# SparkFun_Stepoko.net
KiCad netlist of a schematic drawn in EAGLE
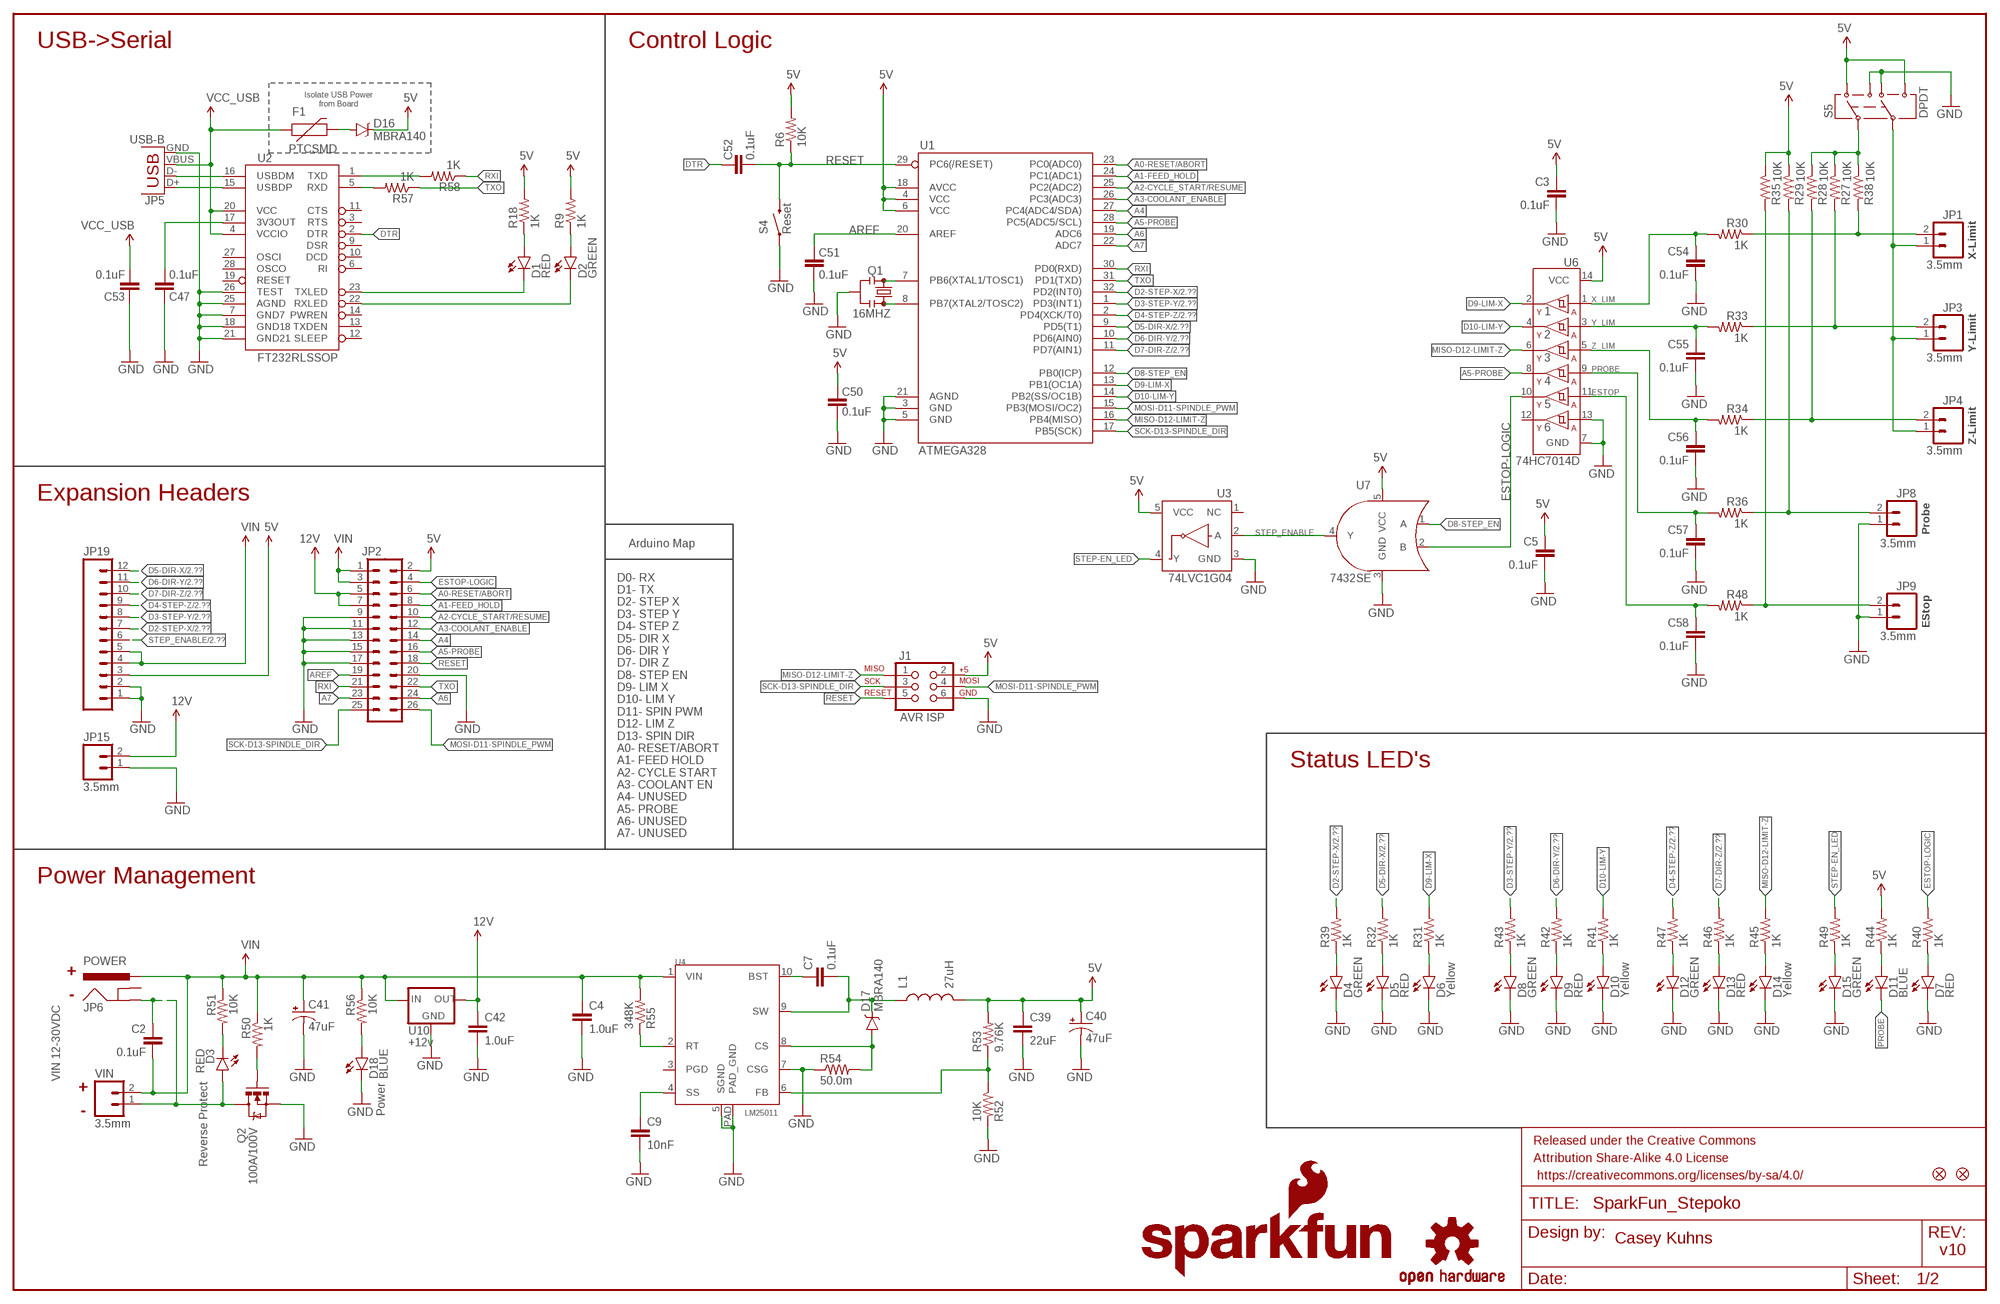
[diagram p0: schematic, sheet 1]
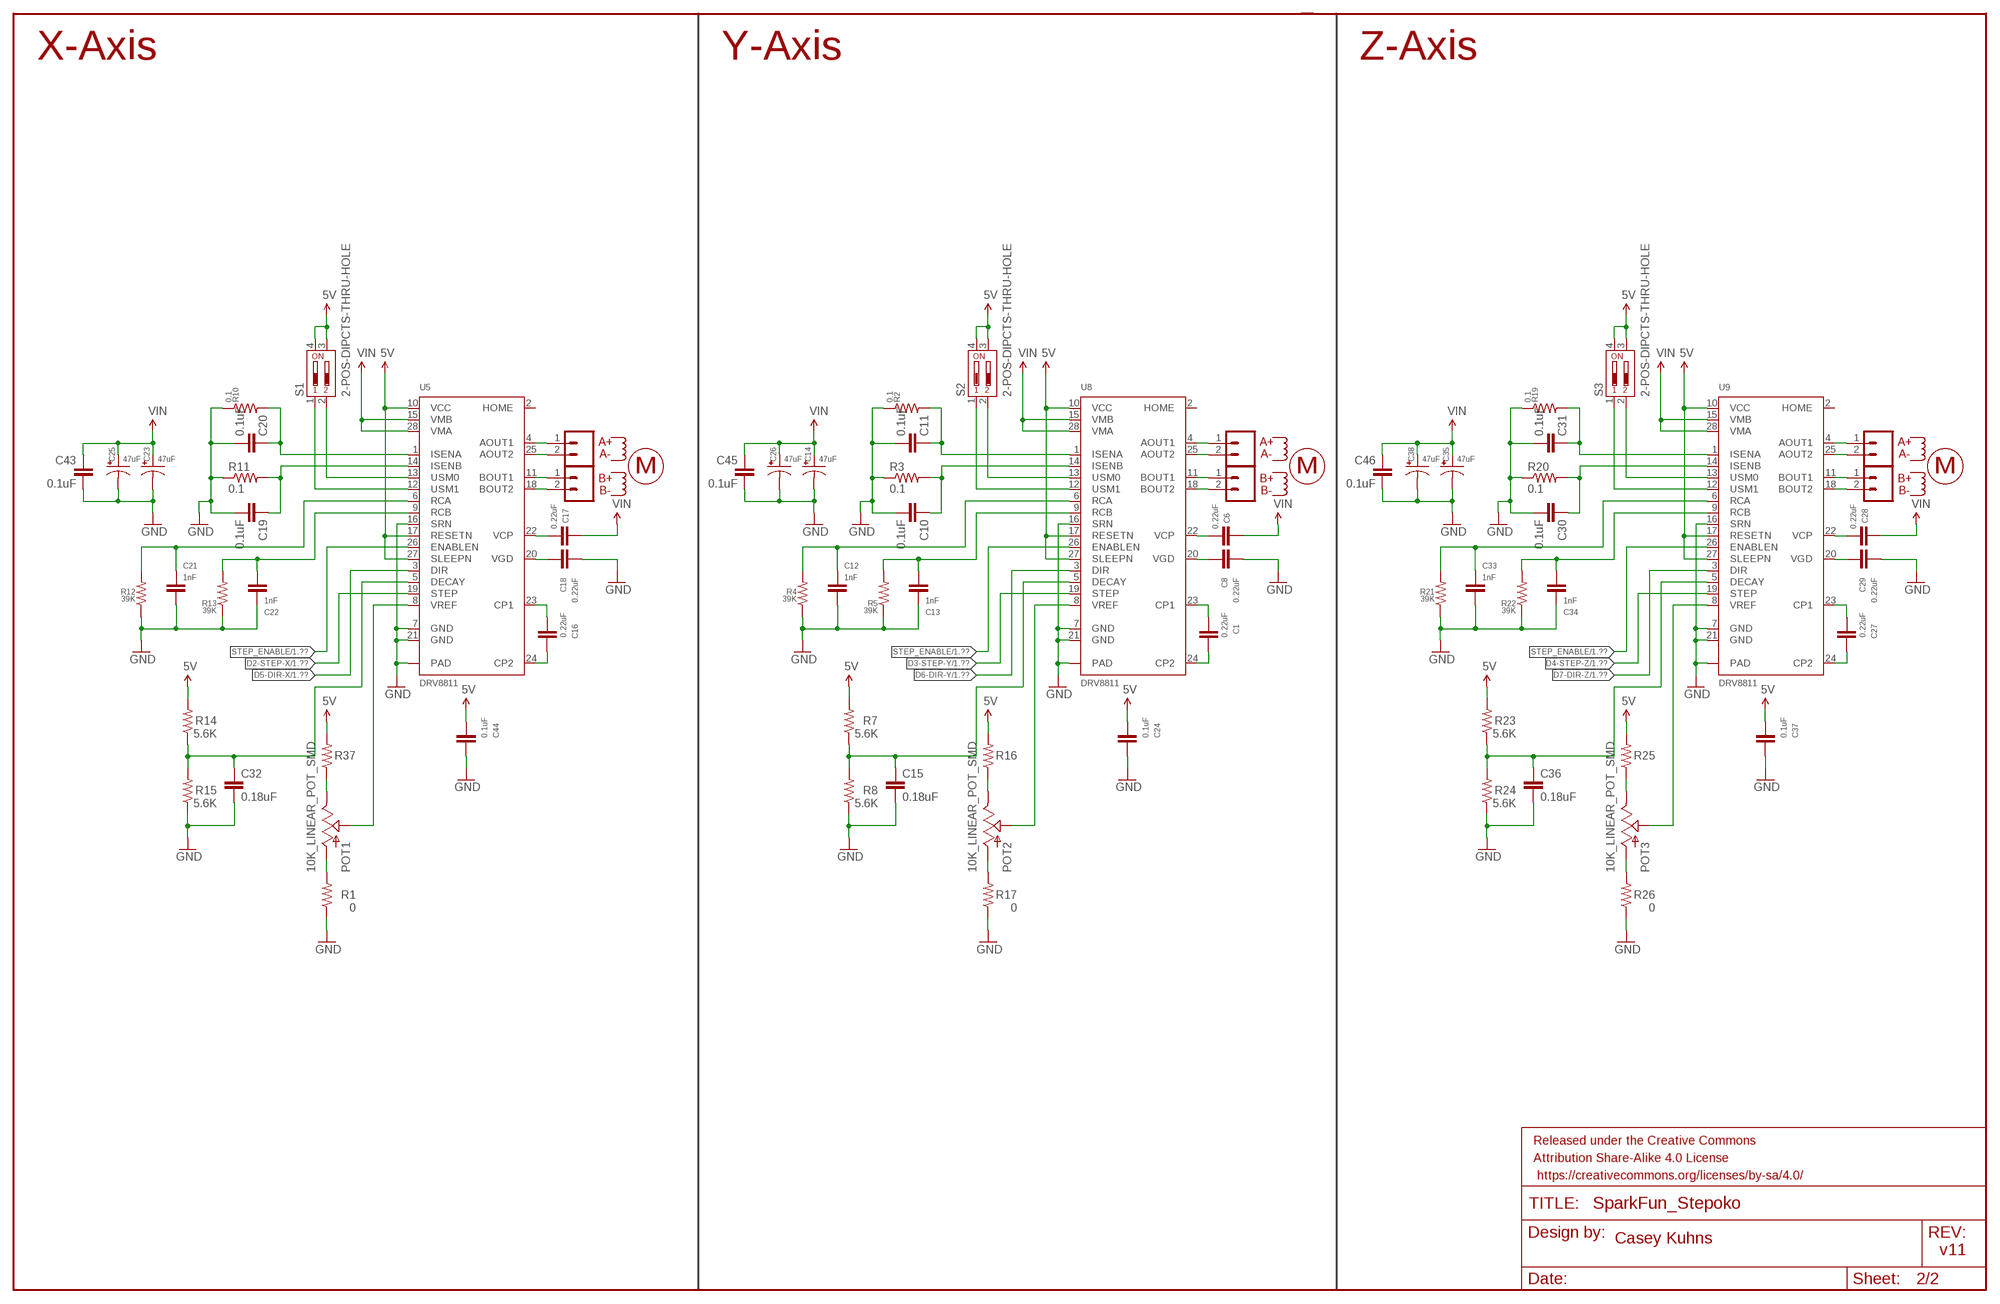
[diagram p1: schematic, sheet 2]

(export (version "E")
  (design (tool "Eeschema 10.0.6"))
  (components
    (comp (ref "C1")
      (value "0.22uF")
      (footprint "eagle-import:0603-CAP")
      (libsource (lib "eagle-import") (part "0.22UF50V-20%,+80%(0603)"))
    )
    (comp (ref "C6")
      (value "0.22uF")
      (footprint "eagle-import:0603-CAP")
      (libsource (lib "eagle-import") (part "0.22UF50V-20%,+80%(0603)"))
    )
    (comp (ref "C8")
      (value "0.22uF")
      (footprint "eagle-import:0603-CAP")
      (libsource (lib "eagle-import") (part "0.22UF50V-20%,+80%(0603)"))
    )
    (comp (ref "C10")
      (value "0.1uF")
      (footprint "eagle-import:0603-CAP")
      (libsource (lib "eagle-import") (part "0.1UF-25V(+80/-20%)(0603)"))
    )
    (comp (ref "C11")
      (value "0.1uF")
      (footprint "eagle-import:0603-CAP")
      (libsource (lib "eagle-import") (part "0.1UF-25V(+80/-20%)(0603)"))
    )
    (comp (ref "C12")
      (value "1nF")
      (footprint "eagle-import:0603-CAP")
      (libsource (lib "eagle-import") (part "1NF/1000PF-50V-10%(0603)"))
    )
    (comp (ref "C13")
      (value "1nF")
      (footprint "eagle-import:0603-CAP")
      (libsource (lib "eagle-import") (part "1NF/1000PF-50V-10%(0603)"))
    )
    (comp (ref "C14")
      (value "47uF")
      (footprint "eagle-import:PANASONIC_D")
      (libsource (lib "eagle-import") (part "47UF-50V-20%(ELECT)"))
    )
    (comp (ref "C15")
      (value "0.18uF")
      (footprint "eagle-import:0603")
      (libsource (lib "eagle-import") (part "0.18UF-10V(+-10%)(0603)"))
    )
    (comp (ref "C16")
      (value "0.22uF")
      (footprint "eagle-import:0603-CAP")
      (libsource (lib "eagle-import") (part "0.22UF50V-20%,+80%(0603)"))
    )
    (comp (ref "C17")
      (value "0.22uF")
      (footprint "eagle-import:0603-CAP")
      (libsource (lib "eagle-import") (part "0.22UF50V-20%,+80%(0603)"))
    )
    (comp (ref "C18")
      (value "0.22uF")
      (footprint "eagle-import:0603-CAP")
      (libsource (lib "eagle-import") (part "0.22UF50V-20%,+80%(0603)"))
    )
    (comp (ref "C19")
      (value "0.1uF")
      (footprint "eagle-import:0603-CAP")
      (libsource (lib "eagle-import") (part "0.1UF-25V(+80/-20%)(0603)"))
    )
    (comp (ref "C20")
      (value "0.1uF")
      (footprint "eagle-import:0603-CAP")
      (libsource (lib "eagle-import") (part "0.1UF-25V(+80/-20%)(0603)"))
    )
    (comp (ref "C21")
      (value "1nF")
      (footprint "eagle-import:0603-CAP")
      (libsource (lib "eagle-import") (part "1NF/1000PF-50V-10%(0603)"))
    )
    (comp (ref "C22")
      (value "1nF")
      (footprint "eagle-import:0603-CAP")
      (libsource (lib "eagle-import") (part "1NF/1000PF-50V-10%(0603)"))
    )
    (comp (ref "C23")
      (value "47uF")
      (footprint "eagle-import:PANASONIC_D")
      (libsource (lib "eagle-import") (part "47UF-50V-20%(ELECT)"))
    )
    (comp (ref "C24")
      (value "0.1uF")
      (footprint "eagle-import:0603-CAP")
      (libsource (lib "eagle-import") (part "0.1UF-25V(+80/-20%)(0603)"))
    )
    (comp (ref "C25")
      (value "47uF")
      (footprint "eagle-import:PANASONIC_D")
      (libsource (lib "eagle-import") (part "47UF-50V-20%(ELECT)"))
    )
    (comp (ref "C26")
      (value "47uF")
      (footprint "eagle-import:PANASONIC_D")
      (libsource (lib "eagle-import") (part "47UF-50V-20%(ELECT)"))
    )
    (comp (ref "C27")
      (value "0.22uF")
      (footprint "eagle-import:0603-CAP")
      (libsource (lib "eagle-import") (part "0.22UF50V-20%,+80%(0603)"))
    )
    (comp (ref "C28")
      (value "0.22uF")
      (footprint "eagle-import:0603-CAP")
      (libsource (lib "eagle-import") (part "0.22UF50V-20%,+80%(0603)"))
    )
    (comp (ref "C29")
      (value "0.22uF")
      (footprint "eagle-import:0603-CAP")
      (libsource (lib "eagle-import") (part "0.22UF50V-20%,+80%(0603)"))
    )
    (comp (ref "C30")
      (value "0.1uF")
      (footprint "eagle-import:0603-CAP")
      (libsource (lib "eagle-import") (part "0.1UF-25V(+80/-20%)(0603)"))
    )
    (comp (ref "C31")
      (value "0.1uF")
      (footprint "eagle-import:0603-CAP")
      (libsource (lib "eagle-import") (part "0.1UF-25V(+80/-20%)(0603)"))
    )
    (comp (ref "C32")
      (value "0.18uF")
      (footprint "eagle-import:0603")
      (libsource (lib "eagle-import") (part "0.18UF-10V(+-10%)(0603)"))
    )
    (comp (ref "C33")
      (value "1nF")
      (footprint "eagle-import:0603-CAP")
      (libsource (lib "eagle-import") (part "1NF/1000PF-50V-10%(0603)"))
    )
    (comp (ref "C34")
      (value "1nF")
      (footprint "eagle-import:0603-CAP")
      (libsource (lib "eagle-import") (part "1NF/1000PF-50V-10%(0603)"))
    )
    (comp (ref "C35")
      (value "47uF")
      (footprint "eagle-import:PANASONIC_D")
      (libsource (lib "eagle-import") (part "47UF-50V-20%(ELECT)"))
    )
    (comp (ref "C36")
      (value "0.18uF")
      (footprint "eagle-import:0603")
      (libsource (lib "eagle-import") (part "0.18UF-10V(+-10%)(0603)"))
    )
    (comp (ref "C37")
      (value "0.1uF")
      (footprint "eagle-import:0603-CAP")
      (libsource (lib "eagle-import") (part "0.1UF-25V(+80/-20%)(0603)"))
    )
    (comp (ref "C38")
      (value "47uF")
      (footprint "eagle-import:PANASONIC_D")
      (libsource (lib "eagle-import") (part "47UF-50V-20%(ELECT)"))
    )
    (comp (ref "C43")
      (value "0.1uF")
      (footprint "eagle-import:0603-CAP")
      (libsource (lib "eagle-import") (part "0.1UF-100V-10%(0603)"))
    )
    (comp (ref "C44")
      (value "0.1uF")
      (footprint "eagle-import:0603-CAP")
      (libsource (lib "eagle-import") (part "0.1UF-25V(+80/-20%)(0603)"))
    )
    (comp (ref "C45")
      (value "0.1uF")
      (footprint "eagle-import:0603-CAP")
      (libsource (lib "eagle-import") (part "0.1UF-100V-10%(0603)"))
    )
    (comp (ref "C46")
      (value "0.1uF")
      (footprint "eagle-import:0603-CAP")
      (libsource (lib "eagle-import") (part "0.1UF-100V-10%(0603)"))
    )
    (comp (ref "FRAME2")
      (value "FRAME-LEDGER")
      (footprint "eagle-import:CREATIVE_COMMONS")
      (fields (field (name "DESIGNER") "Casey Kuhns") (field (name "VERSION") "v02"))
      (libsource (lib "eagle-import") (part "FRAME-LEDGER"))
    )
    (comp (ref "POT1")
      (value "10K_LINEAR_POT_SMD")
      (footprint "eagle-import:TC33X")
      (libsource (lib "eagle-import") (part "10K_LINEAR_POT_SMD"))
    )
    (comp (ref "POT2")
      (value "10K_LINEAR_POT_SMD")
      (footprint "eagle-import:TC33X")
      (libsource (lib "eagle-import") (part "10K_LINEAR_POT_SMD"))
    )
    (comp (ref "POT3")
      (value "10K_LINEAR_POT_SMD")
      (footprint "eagle-import:TC33X")
      (libsource (lib "eagle-import") (part "10K_LINEAR_POT_SMD"))
    )
    (comp (ref "R1")
      (value "0")
      (footprint "eagle-import:0603")
      (libsource (lib "eagle-import") (part "0OHM-1/10W-5%(0603)"))
    )
    (comp (ref "R2")
      (value "0.1")
      (footprint "eagle-import:1210")
      (libsource (lib "eagle-import") (part "0.1OHM-1/2W-1%(1210)"))
    )
    (comp (ref "R3")
      (value "0.1")
      (footprint "eagle-import:1210")
      (libsource (lib "eagle-import") (part "0.1OHM-1/2W-1%(1210)"))
    )
    (comp (ref "R4")
      (value "39K")
      (footprint "eagle-import:0603")
      (libsource (lib "eagle-import") (part "39KOHM-1/10W-1%(0603)"))
    )
    (comp (ref "R5")
      (value "39K")
      (footprint "eagle-import:0603")
      (libsource (lib "eagle-import") (part "39KOHM-1/10W-1%(0603)"))
    )
    (comp (ref "R7")
      (value "5.6K")
      (footprint "eagle-import:0603")
      (libsource (lib "eagle-import") (part "5.6KOHM-1/10W-1%(0603)"))
    )
    (comp (ref "R8")
      (value "5.6K")
      (footprint "eagle-import:0603")
      (libsource (lib "eagle-import") (part "5.6KOHM-1/10W-1%(0603)"))
    )
    (comp (ref "R10")
      (value "0.1")
      (footprint "eagle-import:1210")
      (libsource (lib "eagle-import") (part "0.1OHM-1/2W-1%(1210)"))
    )
    (comp (ref "R11")
      (value "0.1")
      (footprint "eagle-import:1210")
      (libsource (lib "eagle-import") (part "0.1OHM-1/2W-1%(1210)"))
    )
    (comp (ref "R12")
      (value "39K")
      (footprint "eagle-import:0603")
      (libsource (lib "eagle-import") (part "39KOHM-1/10W-1%(0603)"))
    )
    (comp (ref "R13")
      (value "39K")
      (footprint "eagle-import:0603")
      (libsource (lib "eagle-import") (part "39KOHM-1/10W-1%(0603)"))
    )
    (comp (ref "R14")
      (value "5.6K")
      (footprint "eagle-import:0603")
      (libsource (lib "eagle-import") (part "5.6KOHM-1/10W-1%(0603)"))
    )
    (comp (ref "R15")
      (value "5.6K")
      (footprint "eagle-import:0603")
      (libsource (lib "eagle-import") (part "5.6KOHM-1/10W-1%(0603)"))
    )
    (comp (ref "R16")
      (value "10K")
      (footprint "eagle-import:0603-RES")
      (libsource (lib "eagle-import") (part "10KOHM-1/10W-1%(0603)0603"))
    )
    (comp (ref "R17")
      (value "0")
      (footprint "eagle-import:0603")
      (libsource (lib "eagle-import") (part "0OHM-1/10W-5%(0603)"))
    )
    (comp (ref "R19")
      (value "0.1")
      (footprint "eagle-import:1210")
      (libsource (lib "eagle-import") (part "0.1OHM-1/2W-1%(1210)"))
    )
    (comp (ref "R20")
      (value "0.1")
      (footprint "eagle-import:1210")
      (libsource (lib "eagle-import") (part "0.1OHM-1/2W-1%(1210)"))
    )
    (comp (ref "R21")
      (value "39K")
      (footprint "eagle-import:0603")
      (libsource (lib "eagle-import") (part "39KOHM-1/10W-1%(0603)"))
    )
    (comp (ref "R22")
      (value "39K")
      (footprint "eagle-import:0603")
      (libsource (lib "eagle-import") (part "39KOHM-1/10W-1%(0603)"))
    )
    (comp (ref "R23")
      (value "5.6K")
      (footprint "eagle-import:0603")
      (libsource (lib "eagle-import") (part "5.6KOHM-1/10W-1%(0603)"))
    )
    (comp (ref "R24")
      (value "5.6K")
      (footprint "eagle-import:0603")
      (libsource (lib "eagle-import") (part "5.6KOHM-1/10W-1%(0603)"))
    )
    (comp (ref "R25")
      (value "10K")
      (footprint "eagle-import:0603-RES")
      (libsource (lib "eagle-import") (part "10KOHM-1/10W-1%(0603)0603"))
    )
    (comp (ref "R26")
      (value "0")
      (footprint "eagle-import:0603")
      (libsource (lib "eagle-import") (part "0OHM-1/10W-5%(0603)"))
    )
    (comp (ref "R37")
      (value "10K")
      (footprint "eagle-import:0603-RES")
      (libsource (lib "eagle-import") (part "10KOHM-1/10W-1%(0603)0603"))
    )
    (comp (ref "S1")
      (value "2-POS-DIPCTS-THRU-HOLE")
      (footprint "eagle-import:209-2LPST")
      (libsource (lib "eagle-import") (part "2-POS-DIPCTS-THRU-HOLE"))
    )
    (comp (ref "S2")
      (value "2-POS-DIPCTS-THRU-HOLE")
      (footprint "eagle-import:209-2LPST")
      (libsource (lib "eagle-import") (part "2-POS-DIPCTS-THRU-HOLE"))
    )
    (comp (ref "S3")
      (value "2-POS-DIPCTS-THRU-HOLE")
      (footprint "eagle-import:209-2LPST")
      (libsource (lib "eagle-import") (part "2-POS-DIPCTS-THRU-HOLE"))
    )
    (comp (ref "U5")
      (value "DRV8811")
      (footprint "eagle-import:HTSSOP28")
      (libsource (lib "eagle-import") (part "DRV8811"))
    )
    (comp (ref "U8")
      (value "DRV8811")
      (footprint "eagle-import:HTSSOP28")
      (libsource (lib "eagle-import") (part "DRV8811"))
    )
    (comp (ref "U9")
      (value "DRV8811")
      (footprint "eagle-import:HTSSOP28")
      (libsource (lib "eagle-import") (part "DRV8811"))
    )
    (comp (ref "X-A")
      (value "3.5mm")
      (footprint "eagle-import:SCREWTERMINAL-3.5MM-2_LOCK")
      (libsource (lib "eagle-import") (part "M023.5MM_LOCK"))
    )
    (comp (ref "X-B")
      (value "3.5mm")
      (footprint "eagle-import:SCREWTERMINAL-3.5MM-2_LOCK")
      (libsource (lib "eagle-import") (part "M023.5MM_LOCK"))
    )
    (comp (ref "Y-A")
      (value "3.5mm")
      (footprint "eagle-import:SCREWTERMINAL-3.5MM-2_LOCK")
      (libsource (lib "eagle-import") (part "M023.5MM_LOCK"))
    )
    (comp (ref "Y-B")
      (value "3.5mm")
      (footprint "eagle-import:SCREWTERMINAL-3.5MM-2_LOCK")
      (libsource (lib "eagle-import") (part "M023.5MM_LOCK"))
    )
    (comp (ref "Z-A")
      (value "3.5mm")
      (footprint "eagle-import:SCREWTERMINAL-3.5MM-2_LOCK")
      (libsource (lib "eagle-import") (part "M023.5MM_LOCK"))
    )
    (comp (ref "Z-B")
      (value "3.5mm")
      (footprint "eagle-import:SCREWTERMINAL-3.5MM-2_LOCK")
      (libsource (lib "eagle-import") (part "M023.5MM_LOCK"))
    )
    (comp (ref "C2")
      (value "0.1uF")
      (footprint "eagle-import:0603-CAP")
      (libsource (lib "eagle-import") (part "0.1UF-100V-10%(0603)"))
    )
    (comp (ref "C3")
      (value "0.1uF")
      (footprint "eagle-import:0603-CAP")
      (libsource (lib "eagle-import") (part "0.1UF-25V(+80/-20%)(0603)"))
    )
    (comp (ref "C4")
      (value "1.0uF")
      (footprint "eagle-import:1206-CAP")
      (libsource (lib "eagle-import") (part "1.0UF50V10%(1206)"))
    )
    (comp (ref "C5")
      (value "0.1uF")
      (footprint "eagle-import:0603-CAP")
      (libsource (lib "eagle-import") (part "0.1UF-25V(+80/-20%)(0603)"))
    )
    (comp (ref "C7")
      (value "0.1uF")
      (footprint "eagle-import:0603-CAP")
      (libsource (lib "eagle-import") (part "0.1UF-25V(+80/-20%)(0603)"))
    )
    (comp (ref "C9")
      (value "10nF")
      (footprint "eagle-import:0603-CAP")
      (libsource (lib "eagle-import") (part "10NF/10000PF-50V-10%(0603)"))
    )
    (comp (ref "C39")
      (value "22uF")
      (footprint "eagle-import:1210")
      (libsource (lib "eagle-import") (part "22UF-16V-20%-(1210)"))
    )
    (comp (ref "C40")
      (value "47uF")
      (footprint "eagle-import:PANASONIC_D")
      (libsource (lib "eagle-import") (part "47UF-50V-20%(ELECT)"))
    )
    (comp (ref "C41")
      (value "47uF")
      (footprint "eagle-import:PANASONIC_D")
      (libsource (lib "eagle-import") (part "47UF-50V-20%(ELECT)"))
    )
    (comp (ref "C42")
      (value "1.0uF")
      (footprint "eagle-import:1206-CAP")
      (libsource (lib "eagle-import") (part "1.0UF50V10%(1206)"))
    )
    (comp (ref "C47")
      (value "0.1uF")
      (footprint "eagle-import:0603-CAP")
      (libsource (lib "eagle-import") (part "0.1UF-25V(+80/-20%)(0603)"))
    )
    (comp (ref "C50")
      (value "0.1uF")
      (footprint "eagle-import:0603-CAP")
      (libsource (lib "eagle-import") (part "0.1UF-25V(+80/-20%)(0603)"))
    )
    (comp (ref "C51")
      (value "0.1uF")
      (footprint "eagle-import:0603-CAP")
      (libsource (lib "eagle-import") (part "0.1UF-25V(+80/-20%)(0603)"))
    )
    (comp (ref "C52")
      (value "0.1uF")
      (footprint "eagle-import:0603-CAP")
      (libsource (lib "eagle-import") (part "0.1UF-25V(+80/-20%)(0603)"))
    )
    (comp (ref "C53")
      (value "0.1uF")
      (footprint "eagle-import:0603-CAP")
      (libsource (lib "eagle-import") (part "0.1UF-25V(+80/-20%)(0603)"))
    )
    (comp (ref "C54")
      (value "0.1uF")
      (footprint "eagle-import:0603-CAP")
      (libsource (lib "eagle-import") (part "0.1UF-25V(+80/-20%)(0603)"))
    )
    (comp (ref "C55")
      (value "0.1uF")
      (footprint "eagle-import:0603-CAP")
      (libsource (lib "eagle-import") (part "0.1UF-25V(+80/-20%)(0603)"))
    )
    (comp (ref "C56")
      (value "0.1uF")
      (footprint "eagle-import:0603-CAP")
      (libsource (lib "eagle-import") (part "0.1UF-25V(+80/-20%)(0603)"))
    )
    (comp (ref "C57")
      (value "0.1uF")
      (footprint "eagle-import:0603-CAP")
      (libsource (lib "eagle-import") (part "0.1UF-25V(+80/-20%)(0603)"))
    )
    (comp (ref "C58")
      (value "0.1uF")
      (footprint "eagle-import:0603-CAP")
      (libsource (lib "eagle-import") (part "0.1UF-25V(+80/-20%)(0603)"))
    )
    (comp (ref "D1")
      (value "RED")
      (footprint "eagle-import:LED-1206")
      (libsource (lib "eagle-import") (part "LED-REDLILYPAD"))
    )
    (comp (ref "D2")
      (value "GREEN")
      (footprint "eagle-import:LED-1206")
      (libsource (lib "eagle-import") (part "LED-GREENLILYPAD"))
    )
    (comp (ref "D3")
      (value "RED")
      (footprint "eagle-import:LED-1206")
      (libsource (lib "eagle-import") (part "LED-REDLILYPAD"))
    )
    (comp (ref "D4")
      (value "GREEN")
      (footprint "eagle-import:LED-1206")
      (libsource (lib "eagle-import") (part "LED-GREENLILYPAD"))
    )
    (comp (ref "D5")
      (value "RED")
      (footprint "eagle-import:LED-1206")
      (libsource (lib "eagle-import") (part "LED-REDLILYPAD"))
    )
    (comp (ref "D6")
      (value "Yellow")
      (footprint "eagle-import:LED-1206")
      (libsource (lib "eagle-import") (part "LED-YELLOWLILYPAD"))
    )
    (comp (ref "D7")
      (value "RED")
      (footprint "eagle-import:LED-1206")
      (libsource (lib "eagle-import") (part "LED-REDLILYPAD"))
    )
    (comp (ref "D8")
      (value "GREEN")
      (footprint "eagle-import:LED-1206")
      (libsource (lib "eagle-import") (part "LED-GREENLILYPAD"))
    )
    (comp (ref "D9")
      (value "RED")
      (footprint "eagle-import:LED-1206")
      (libsource (lib "eagle-import") (part "LED-REDLILYPAD"))
    )
    (comp (ref "D10")
      (value "Yellow")
      (footprint "eagle-import:LED-1206")
      (libsource (lib "eagle-import") (part "LED-YELLOWLILYPAD"))
    )
    (comp (ref "D11")
      (value "BLUE")
      (footprint "eagle-import:LED-1206")
      (libsource (lib "eagle-import") (part "LED-BLUE1206"))
    )
    (comp (ref "D12")
      (value "GREEN")
      (footprint "eagle-import:LED-1206")
      (libsource (lib "eagle-import") (part "LED-GREENLILYPAD"))
    )
    (comp (ref "D13")
      (value "RED")
      (footprint "eagle-import:LED-1206")
      (libsource (lib "eagle-import") (part "LED-REDLILYPAD"))
    )
    (comp (ref "D14")
      (value "Yellow")
      (footprint "eagle-import:LED-1206")
      (libsource (lib "eagle-import") (part "LED-YELLOWLILYPAD"))
    )
    (comp (ref "D15")
      (value "GREEN")
      (footprint "eagle-import:LED-1206")
      (libsource (lib "eagle-import") (part "LED-GREENLILYPAD"))
    )
    (comp (ref "D16")
      (value "MBRA140")
      (footprint "eagle-import:SMA-DIODE")
      (libsource (lib "eagle-import") (part "DIODE-SCHOTTKY-MBRA140"))
    )
    (comp (ref "D17")
      (value "MBRA140")
      (footprint "eagle-import:SMA-DIODE")
      (libsource (lib "eagle-import") (part "DIODE-SCHOTTKY-MBRA140"))
    )
    (comp (ref "D18")
      (value "BLUE")
      (footprint "eagle-import:LED-1206")
      (libsource (lib "eagle-import") (part "LED-BLUE1206"))
    )
    (comp (ref "F1")
      (value "PTCSMD")
      (footprint "eagle-import:PTC-1206")
      (libsource (lib "eagle-import") (part "PTCSMD"))
    )
    (comp (ref "FID1")
      (value "FIDUCIAL1X2")
      (footprint "eagle-import:FIDUCIAL-1X2")
      (libsource (lib "eagle-import") (part "FIDUCIAL1X2"))
    )
    (comp (ref "FID2")
      (value "FIDUCIAL1X2")
      (footprint "eagle-import:FIDUCIAL-1X2")
      (libsource (lib "eagle-import") (part "FIDUCIAL1X2"))
    )
    (comp (ref "FRAME1")
      (value "FRAME-LEDGER")
      (footprint "eagle-import:CREATIVE_COMMONS")
      (fields (field (name "DESIGNER") "Casey Kuhns") (field (name "VERSION") "v02"))
      (libsource (lib "eagle-import") (part "FRAME-LEDGER"))
    )
    (comp (ref "J1")
      (value "AVR ISP")
      (footprint "eagle-import:2X3")
      (libsource (lib "eagle-import") (part "AVR_SPI_PRG_6PTH"))
    )
    (comp (ref "JP1")
      (value "3.5mm")
      (footprint "eagle-import:SCREWTERMINAL-3.5MM-2_LOCK")
      (libsource (lib "eagle-import") (part "M023.5MM_LOCK"))
    )
    (comp (ref "JP2")
      (value "M13X22X13")
      (footprint "eagle-import:2X13")
      (libsource (lib "eagle-import") (part "M13X22X13"))
    )
    (comp (ref "JP3")
      (value "3.5mm")
      (footprint "eagle-import:SCREWTERMINAL-3.5MM-2_LOCK")
      (libsource (lib "eagle-import") (part "M023.5MM_LOCK"))
    )
    (comp (ref "JP4")
      (value "3.5mm")
      (footprint "eagle-import:SCREWTERMINAL-3.5MM-2_LOCK")
      (libsource (lib "eagle-import") (part "M023.5MM_LOCK"))
    )
    (comp (ref "JP5")
      (value "USB-B")
      (footprint "eagle-import:USB-B-PTH")
      (libsource (lib "eagle-import") (part "USBPTH"))
    )
    (comp (ref "JP6")
      (value "POWER")
      (footprint "eagle-import:POWER_JACK_PTH_LOCK")
      (libsource (lib "eagle-import") (part "POWER_JACKPTH_LOCK"))
    )
    (comp (ref "JP8")
      (value "3.5mm")
      (footprint "eagle-import:SCREWTERMINAL-3.5MM-2_LOCK")
      (libsource (lib "eagle-import") (part "M023.5MM_LOCK"))
    )
    (comp (ref "JP9")
      (value "3.5mm")
      (footprint "eagle-import:SCREWTERMINAL-3.5MM-2_LOCK")
      (libsource (lib "eagle-import") (part "M023.5MM_LOCK"))
    )
    (comp (ref "JP15")
      (value "3.5mm")
      (footprint "eagle-import:SCREWTERMINAL-3.5MM-2_LOCK")
      (libsource (lib "eagle-import") (part "M023.5MM_LOCK"))
    )
    (comp (ref "JP19")
      (value "M12PTH")
      (footprint "eagle-import:1X12")
      (libsource (lib "eagle-import") (part "M12PTH"))
    )
    (comp (ref "L1")
      (value "27uH")
      (footprint "eagle-import:INDUCTOR_SDR1307")
      (libsource (lib "eagle-import") (part "INDUCTORSDR13-7-270ML"))
    )
    (comp (ref "LOGO1")
      (value "OSHW-LOGOM")
      (footprint "eagle-import:OSHW-LOGO-M")
      (libsource (lib "eagle-import") (part "OSHW-LOGOM"))
    )
    (comp (ref "LOGO3")
      (value "SFE_LOGO_NAME_FLAME.2_INCH")
      (footprint "eagle-import:SFE_LOGO_NAME_FLAME_.2")
      (libsource (lib "eagle-import") (part "SFE_LOGO_NAME_FLAME.2_INCH"))
    )
    (comp (ref "Q1")
      (value "16MHZ")
      (footprint "eagle-import:RESONATOR-SMD")
      (libsource (lib "eagle-import") (part "RESONATOR16MHZ"))
    )
    (comp (ref "Q2")
      (value "100A/100V")
      (footprint "eagle-import:TO-263_D2PAK")
      (libsource (lib "eagle-import") (part "MOSFET-NCHANNELPSMN7R0"))
    )
    (comp (ref "R6")
      (value "10K")
      (footprint "eagle-import:0603-RES")
      (libsource (lib "eagle-import") (part "10KOHM-1/10W-1%(0603)0603"))
    )
    (comp (ref "R9")
      (value "1K")
      (footprint "eagle-import:0603-RES@1")
      (libsource (lib "eagle-import") (part "1KOHM1/10W1%(0603)"))
    )
    (comp (ref "R18")
      (value "1K")
      (footprint "eagle-import:0603-RES@1")
      (libsource (lib "eagle-import") (part "1KOHM1/10W1%(0603)"))
    )
    (comp (ref "R27")
      (value "10K")
      (footprint "eagle-import:0603-RES")
      (libsource (lib "eagle-import") (part "10KOHM-1/10W-1%(0603)0603"))
    )
    (comp (ref "R28")
      (value "10K")
      (footprint "eagle-import:0603-RES")
      (libsource (lib "eagle-import") (part "10KOHM-1/10W-1%(0603)0603"))
    )
    (comp (ref "R29")
      (value "10K")
      (footprint "eagle-import:0603-RES")
      (libsource (lib "eagle-import") (part "10KOHM-1/10W-1%(0603)0603"))
    )
    (comp (ref "R30")
      (value "1K")
      (footprint "eagle-import:0603-RES@1")
      (libsource (lib "eagle-import") (part "1KOHM1/10W1%(0603)"))
    )
    (comp (ref "R31")
      (value "1K")
      (footprint "eagle-import:0603-RES")
      (libsource (lib "eagle-import") (part "1KOHM-1/10W-1%(0603)"))
    )
    (comp (ref "R32")
      (value "1K")
      (footprint "eagle-import:0603-RES")
      (libsource (lib "eagle-import") (part "1KOHM-1/10W-1%(0603)"))
    )
    (comp (ref "R33")
      (value "1K")
      (footprint "eagle-import:0603-RES@1")
      (libsource (lib "eagle-import") (part "1KOHM1/10W1%(0603)"))
    )
    (comp (ref "R34")
      (value "1K")
      (footprint "eagle-import:0603-RES@1")
      (libsource (lib "eagle-import") (part "1KOHM1/10W1%(0603)"))
    )
    (comp (ref "R35")
      (value "10K")
      (footprint "eagle-import:0603-RES")
      (libsource (lib "eagle-import") (part "10KOHM-1/10W-1%(0603)0603"))
    )
    (comp (ref "R36")
      (value "1K")
      (footprint "eagle-import:0603-RES@1")
      (libsource (lib "eagle-import") (part "1KOHM1/10W1%(0603)"))
    )
    (comp (ref "R38")
      (value "10K")
      (footprint "eagle-import:0603-RES")
      (libsource (lib "eagle-import") (part "10KOHM-1/10W-1%(0603)0603"))
    )
    (comp (ref "R39")
      (value "1K")
      (footprint "eagle-import:0603-RES")
      (libsource (lib "eagle-import") (part "1KOHM-1/10W-1%(0603)"))
    )
    (comp (ref "R40")
      (value "1K")
      (footprint "eagle-import:0603-RES")
      (libsource (lib "eagle-import") (part "1KOHM-1/10W-1%(0603)"))
    )
    (comp (ref "R41")
      (value "1K")
      (footprint "eagle-import:0603-RES")
      (libsource (lib "eagle-import") (part "1KOHM-1/10W-1%(0603)"))
    )
    (comp (ref "R42")
      (value "1K")
      (footprint "eagle-import:0603-RES")
      (libsource (lib "eagle-import") (part "1KOHM-1/10W-1%(0603)"))
    )
    (comp (ref "R43")
      (value "1K")
      (footprint "eagle-import:0603-RES")
      (libsource (lib "eagle-import") (part "1KOHM-1/10W-1%(0603)"))
    )
    (comp (ref "R44")
      (value "1K")
      (footprint "eagle-import:0603-RES")
      (libsource (lib "eagle-import") (part "1KOHM-1/10W-1%(0603)"))
    )
    (comp (ref "R45")
      (value "1K")
      (footprint "eagle-import:0603-RES")
      (libsource (lib "eagle-import") (part "1KOHM-1/10W-1%(0603)"))
    )
    (comp (ref "R46")
      (value "1K")
      (footprint "eagle-import:0603-RES")
      (libsource (lib "eagle-import") (part "1KOHM-1/10W-1%(0603)"))
    )
    (comp (ref "R47")
      (value "1K")
      (footprint "eagle-import:0603-RES")
      (libsource (lib "eagle-import") (part "1KOHM-1/10W-1%(0603)"))
    )
    (comp (ref "R48")
      (value "1K")
      (footprint "eagle-import:0603-RES@1")
      (libsource (lib "eagle-import") (part "1KOHM1/10W1%(0603)"))
    )
    (comp (ref "R49")
      (value "1K")
      (footprint "eagle-import:0603-RES")
      (libsource (lib "eagle-import") (part "1KOHM-1/10W-1%(0603)"))
    )
    (comp (ref "R50")
      (value "1K")
      (footprint "eagle-import:0603-RES@1")
      (libsource (lib "eagle-import") (part "1KOHM1/10W1%(0603)"))
    )
    (comp (ref "R51")
      (value "10K")
      (footprint "eagle-import:0603-RES")
      (libsource (lib "eagle-import") (part "10KOHM-1/10W-1%(0603)0603"))
    )
    (comp (ref "R52")
      (value "10K")
      (footprint "eagle-import:0603-RES")
      (libsource (lib "eagle-import") (part "10KOHM-1/10W-1%(0603)0603"))
    )
    (comp (ref "R53")
      (value "9.76K")
      (footprint "eagle-import:0603")
      (libsource (lib "eagle-import") (part "9.76KOHM-1/10W-1%(0603)"))
    )
    (comp (ref "R54")
      (value "50.0m")
      (footprint "eagle-import:0603")
      (libsource (lib "eagle-import") (part "0.05OHM-1/5W-1%(0603)"))
    )
    (comp (ref "R55")
      (value "348K")
      (footprint "eagle-import:0603")
      (libsource (lib "eagle-import") (part "348KOHM-1/10W-1%(0603)"))
    )
    (comp (ref "R56")
      (value "10K")
      (footprint "eagle-import:0603-RES")
      (libsource (lib "eagle-import") (part "10KOHM-1/10W-1%(0603)0603"))
    )
    (comp (ref "R57")
      (value "1K")
      (footprint "eagle-import:0603-RES@1")
      (libsource (lib "eagle-import") (part "1KOHM1/10W1%(0603)"))
    )
    (comp (ref "R58")
      (value "1K")
      (footprint "eagle-import:0603-RES@1")
      (libsource (lib "eagle-import") (part "1KOHM1/10W1%(0603)"))
    )
    (comp (ref "S4")
      (value "Reset")
      (footprint "eagle-import:TACTILE-SWITCH-SMD")
      (libsource (lib "eagle-import") (part "SWITCH-MOMENTARY-2SMD"))
    )
    (comp (ref "S5")
      (value "DPDT")
      (footprint "eagle-import:AYZ0202")
      (libsource (lib "eagle-import") (part "SWITCH-DPDTAYZ0202"))
    )
    (comp (ref "U1")
      (value "ATMEGA328")
      (footprint "eagle-import:TQFP32-08@1")
      (libsource (lib "eagle-import") (part "ATMEGA328_SMT"))
    )
    (comp (ref "U2")
      (value "FT232RLSSOP")
      (footprint "eagle-import:SSOP28DB")
      (libsource (lib "eagle-import") (part "FT232RLSSOP"))
    )
    (comp (ref "U3")
      (value "74LVC1G04")
      (footprint "eagle-import:SOT353")
      (libsource (lib "eagle-import") (part "INVERTER_SOT353-5"))
    )
    (comp (ref "U4")
      (value "LM25011")
      (footprint "eagle-import:HVSS0P-10")
      (libsource (lib "eagle-import") (part "LM25011"))
    )
    (comp (ref "U6")
      (value "74HC7014D")
      (footprint "eagle-import:SOIC-14")
      (libsource (lib "eagle-import") (part "74HC7014D"))
    )
    (comp (ref "U7")
      (value "7432SE")
      (footprint "eagle-import:SOT353")
      (libsource (lib "eagle-import") (part "7432SE"))
    )
    (comp (ref "U10")
      (value "+12v")
      (footprint "eagle-import:TO-252")
      (libsource (lib "eagle-import") (part "V_REG_78XX7812"))
    )
    (comp (ref "VIN")
      (value "3.5mm")
      (footprint "eagle-import:SCREWTERMINAL-3.5MM-2_LOCK")
      (libsource (lib "eagle-import") (part "M023.5MM_LOCK"))
    )
  )
  (nets
    (net (code "1") (name "5V") (class "Default")
      (node (ref "C24") (pin "1") (pinfunction "1_1") (pintype "passive"))
      (node (ref "C3") (pin "1") (pinfunction "1_1") (pintype "passive"))
      (node (ref "C37") (pin "1") (pinfunction "1_1") (pintype "passive"))
      (node (ref "C39") (pin "1") (pinfunction "1_1") (pintype "passive"))
      (node (ref "C40") (pin "+") (pinfunction "+_+") (pintype "passive"))
      (node (ref "C44") (pin "1") (pinfunction "1_1") (pintype "passive"))
      (node (ref "C5") (pin "1") (pinfunction "1_1") (pintype "passive"))
      (node (ref "C50") (pin "2") (pinfunction "2_2") (pintype "passive"))
      (node (ref "D16") (pin "C") (pinfunction "C_C") (pintype "passive"))
      (node (ref "J1") (pin "2") (pinfunction "2_2") (pintype "passive"))
      (node (ref "JP19") (pin "3") (pinfunction "3_3") (pintype "passive"))
      (node (ref "JP2") (pin "2") (pinfunction "2_2") (pintype "passive"))
      (node (ref "L1") (pin "P$2") (pinfunction "2_P$2") (pintype "passive"))
      (node (ref "R14") (pin "2") (pinfunction "2_2") (pintype "passive"))
      (node (ref "R16") (pin "2") (pinfunction "2_2") (pintype "passive"))
      (node (ref "R18") (pin "2") (pinfunction "2_2") (pintype "passive"))
      (node (ref "R23") (pin "2") (pinfunction "2_2") (pintype "passive"))
      (node (ref "R25") (pin "2") (pinfunction "2_2") (pintype "passive"))
      (node (ref "R29") (pin "1") (pinfunction "1_1") (pintype "passive"))
      (node (ref "R35") (pin "1") (pinfunction "1_1") (pintype "passive"))
      (node (ref "R37") (pin "2") (pinfunction "2_2") (pintype "passive"))
      (node (ref "R44") (pin "2") (pinfunction "2_2") (pintype "passive"))
      (node (ref "R53") (pin "2") (pinfunction "2_2") (pintype "passive"))
      (node (ref "R6") (pin "2") (pinfunction "2_2") (pintype "passive"))
      (node (ref "R7") (pin "2") (pinfunction "2_2") (pintype "passive"))
      (node (ref "R9") (pin "2") (pinfunction "2_2") (pintype "passive"))
      (node (ref "S1") (pin "3") (pinfunction "P$3_3") (pintype "bidirectional"))
      (node (ref "S1") (pin "4") (pinfunction "P$4_4") (pintype "bidirectional"))
      (node (ref "S2") (pin "3") (pinfunction "P$3_3") (pintype "bidirectional"))
      (node (ref "S2") (pin "4") (pinfunction "P$4_4") (pintype "bidirectional"))
      (node (ref "S3") (pin "3") (pinfunction "P$3_3") (pintype "bidirectional"))
      (node (ref "S3") (pin "4") (pinfunction "P$4_4") (pintype "bidirectional"))
      (node (ref "S5") (pin "1") (pinfunction "1_1") (pintype "bidirectional"))
      (node (ref "S5") (pin "6") (pinfunction "6_6") (pintype "bidirectional"))
      (node (ref "U1") (pin "18") (pinfunction "AVCC_18") (pintype "bidirectional"))
      (node (ref "U1") (pin "4") (pinfunction "VCC_4") (pintype "bidirectional"))
      (node (ref "U1") (pin "6") (pinfunction "VCC_6") (pintype "bidirectional"))
      (node (ref "U3") (pin "5") (pinfunction "VCC_5") (pintype "bidirectional"))
      (node (ref "U5") (pin "10") (pinfunction "VCC_10") (pintype "bidirectional"))
      (node (ref "U5") (pin "17") (pinfunction "RESETN_17") (pintype "bidirectional"))
      (node (ref "U5") (pin "27") (pinfunction "SLEEPN_27") (pintype "bidirectional"))
      (node (ref "U6") (pin "14") (pinfunction "VCC_14") (pintype "power_in"))
      (node (ref "U7") (pin "5") (pinfunction "VCC_5") (pintype "bidirectional"))
      (node (ref "U8") (pin "10") (pinfunction "VCC_10") (pintype "bidirectional"))
      (node (ref "U8") (pin "17") (pinfunction "RESETN_17") (pintype "bidirectional"))
      (node (ref "U8") (pin "27") (pinfunction "SLEEPN_27") (pintype "bidirectional"))
      (node (ref "U9") (pin "10") (pinfunction "VCC_10") (pintype "bidirectional"))
      (node (ref "U9") (pin "17") (pinfunction "RESETN_17") (pintype "bidirectional"))
      (node (ref "U9") (pin "27") (pinfunction "SLEEPN_27") (pintype "bidirectional"))
    )
    (net (code "2") (name "A0-RESET{slash}ABORT") (class "Default")
      (node (ref "JP2") (pin "6") (pinfunction "6_6") (pintype "passive"))
      (node (ref "U1") (pin "23") (pinfunction "PC0(ADC0)_23") (pintype "bidirectional"))
    )
    (net (code "3") (name "A1-FEED_HOLD") (class "Default")
      (node (ref "JP2") (pin "8") (pinfunction "8_8") (pintype "passive"))
      (node (ref "U1") (pin "24") (pinfunction "PC1(ADC1)_24") (pintype "bidirectional"))
    )
    (net (code "4") (name "A2-CYCLE_START{slash}RESUME") (class "Default")
      (node (ref "JP2") (pin "10") (pinfunction "10_10") (pintype "passive"))
      (node (ref "U1") (pin "25") (pinfunction "PC2(ADC2)_25") (pintype "bidirectional"))
    )
    (net (code "5") (name "A3-COOLANT_ENABLE") (class "Default")
      (node (ref "JP2") (pin "12") (pinfunction "12_12") (pintype "passive"))
      (node (ref "U1") (pin "26") (pinfunction "PC3(ADC3)_26") (pintype "bidirectional"))
    )
    (net (code "6") (name "A4") (class "Default")
      (node (ref "JP2") (pin "14") (pinfunction "14_14") (pintype "passive"))
      (node (ref "U1") (pin "27") (pinfunction "PC4(ADC4/SDA)_27") (pintype "bidirectional"))
    )
    (net (code "7") (name "A5-PROBE") (class "Default")
      (node (ref "JP2") (pin "16") (pinfunction "16_16") (pintype "passive"))
      (node (ref "U1") (pin "28") (pinfunction "PC5(ADC5/SCL)_28") (pintype "bidirectional"))
      (node (ref "U6") (pin "8") (pinfunction "4Y_8") (pintype "output"))
    )
    (net (code "8") (name "A6") (class "Default")
      (node (ref "JP2") (pin "24") (pinfunction "24_24") (pintype "passive"))
      (node (ref "U1") (pin "19") (pinfunction "ADC6_19") (pintype "bidirectional"))
    )
    (net (code "9") (name "A7") (class "Default")
      (node (ref "JP2") (pin "23") (pinfunction "23_23") (pintype "passive"))
      (node (ref "U1") (pin "22") (pinfunction "ADC7_22") (pintype "bidirectional"))
    )
    (net (code "10") (name "AREF") (class "Default")
      (node (ref "C51") (pin "2") (pinfunction "2_2") (pintype "passive"))
      (node (ref "JP2") (pin "19") (pinfunction "19_19") (pintype "passive"))
      (node (ref "U1") (pin "20") (pinfunction "AREF_20") (pintype "bidirectional"))
    )
    (net (code "11") (name "D2-STEP-X") (class "Default")
      (node (ref "JP19") (pin "7") (pinfunction "7_7") (pintype "passive"))
      (node (ref "R39") (pin "2") (pinfunction "2_2") (pintype "passive"))
      (node (ref "U1") (pin "32") (pinfunction "PD2(INT0)_32") (pintype "bidirectional"))
      (node (ref "U5") (pin "19") (pinfunction "STEP_19") (pintype "bidirectional"))
    )
    (net (code "12") (name "D3-STEP-Y") (class "Default")
      (node (ref "JP19") (pin "8") (pinfunction "8_8") (pintype "passive"))
      (node (ref "R43") (pin "2") (pinfunction "2_2") (pintype "passive"))
      (node (ref "U1") (pin "1") (pinfunction "PD3(INT1)_1") (pintype "bidirectional"))
      (node (ref "U8") (pin "19") (pinfunction "STEP_19") (pintype "bidirectional"))
    )
    (net (code "13") (name "D4-STEP-Z") (class "Default")
      (node (ref "JP19") (pin "9") (pinfunction "9_9") (pintype "passive"))
      (node (ref "R47") (pin "2") (pinfunction "2_2") (pintype "passive"))
      (node (ref "U1") (pin "2") (pinfunction "PD4(XCK/T0)_2") (pintype "bidirectional"))
      (node (ref "U9") (pin "19") (pinfunction "STEP_19") (pintype "bidirectional"))
    )
    (net (code "14") (name "D5-DIR-X") (class "Default")
      (node (ref "JP19") (pin "12") (pinfunction "12_12") (pintype "passive"))
      (node (ref "R32") (pin "2") (pinfunction "2_2") (pintype "passive"))
      (node (ref "U1") (pin "9") (pinfunction "PD5(T1)_9") (pintype "bidirectional"))
      (node (ref "U5") (pin "3") (pinfunction "DIR_3") (pintype "bidirectional"))
    )
    (net (code "15") (name "D6-DIR-Y") (class "Default")
      (node (ref "JP19") (pin "11") (pinfunction "11_11") (pintype "passive"))
      (node (ref "R42") (pin "2") (pinfunction "2_2") (pintype "passive"))
      (node (ref "U1") (pin "10") (pinfunction "PD6(AIN0)_10") (pintype "bidirectional"))
      (node (ref "U8") (pin "3") (pinfunction "DIR_3") (pintype "bidirectional"))
    )
    (net (code "16") (name "D7-DIR-Z") (class "Default")
      (node (ref "JP19") (pin "10") (pinfunction "10_10") (pintype "passive"))
      (node (ref "R46") (pin "2") (pinfunction "2_2") (pintype "passive"))
      (node (ref "U1") (pin "11") (pinfunction "PD7(AIN1)_11") (pintype "bidirectional"))
      (node (ref "U9") (pin "3") (pinfunction "DIR_3") (pintype "bidirectional"))
    )
    (net (code "17") (name "D8-STEP_EN") (class "Default")
      (node (ref "U1") (pin "12") (pinfunction "PB0(ICP)_12") (pintype "bidirectional"))
      (node (ref "U7") (pin "1") (pinfunction "A_1") (pintype "bidirectional"))
    )
    (net (code "18") (name "D9-LIM-X") (class "Default")
      (node (ref "R31") (pin "2") (pinfunction "2_2") (pintype "passive"))
      (node (ref "U1") (pin "13") (pinfunction "PB1(OC1A)_13") (pintype "bidirectional"))
      (node (ref "U6") (pin "2") (pinfunction "1Y_2") (pintype "output"))
    )
    (net (code "19") (name "D10-LIM-Y") (class "Default")
      (node (ref "R41") (pin "2") (pinfunction "2_2") (pintype "passive"))
      (node (ref "U1") (pin "14") (pinfunction "PB2(SS/OC1B)_14") (pintype "bidirectional"))
      (node (ref "U6") (pin "4") (pinfunction "2Y_4") (pintype "output"))
    )
    (net (code "20") (name "DTR") (class "Default")
      (node (ref "C52") (pin "2") (pinfunction "2_2") (pintype "passive"))
      (node (ref "U2") (pin "2") (pinfunction "DTR_2") (pintype "output"))
    )
    (net (code "21") (name "ESTOP") (class "Default")
      (node (ref "C58") (pin "1") (pinfunction "1_1") (pintype "passive"))
      (node (ref "R48") (pin "2") (pinfunction "2_2") (pintype "passive"))
      (node (ref "U6") (pin "11") (pinfunction "5A_11") (pintype "input"))
    )
    (net (code "22") (name "ESTOP-LOGIC") (class "Default")
      (node (ref "JP2") (pin "4") (pinfunction "4_4") (pintype "passive"))
      (node (ref "R40") (pin "2") (pinfunction "2_2") (pintype "passive"))
      (node (ref "U6") (pin "10") (pinfunction "5Y_10") (pintype "output"))
      (node (ref "U7") (pin "2") (pinfunction "B_2") (pintype "bidirectional"))
    )
    (net (code "23") (name "GND") (class "Default")
      (node (ref "C10") (pin "2") (pinfunction "2_2") (pintype "passive"))
      (node (ref "C11") (pin "2") (pinfunction "2_2") (pintype "passive"))
      (node (ref "C12") (pin "2") (pinfunction "2_2") (pintype "passive"))
      (node (ref "C13") (pin "2") (pinfunction "2_2") (pintype "passive"))
      (node (ref "C14") (pin "-") (pinfunction "-_-") (pintype "passive"))
      (node (ref "C15") (pin "2") (pinfunction "2_2") (pintype "passive"))
      (node (ref "C18") (pin "1") (pinfunction "1_1") (pintype "passive"))
      (node (ref "C19") (pin "2") (pinfunction "2_2") (pintype "passive"))
      (node (ref "C20") (pin "2") (pinfunction "2_2") (pintype "passive"))
      (node (ref "C21") (pin "2") (pinfunction "2_2") (pintype "passive"))
      (node (ref "C22") (pin "2") (pinfunction "2_2") (pintype "passive"))
      (node (ref "C23") (pin "-") (pinfunction "-_-") (pintype "passive"))
      (node (ref "C24") (pin "2") (pinfunction "2_2") (pintype "passive"))
      (node (ref "C25") (pin "-") (pinfunction "-_-") (pintype "passive"))
      (node (ref "C26") (pin "-") (pinfunction "-_-") (pintype "passive"))
      (node (ref "C29") (pin "1") (pinfunction "1_1") (pintype "passive"))
      (node (ref "C3") (pin "2") (pinfunction "2_2") (pintype "passive"))
      (node (ref "C30") (pin "2") (pinfunction "2_2") (pintype "passive"))
      (node (ref "C31") (pin "2") (pinfunction "2_2") (pintype "passive"))
      (node (ref "C32") (pin "2") (pinfunction "2_2") (pintype "passive"))
      (node (ref "C33") (pin "2") (pinfunction "2_2") (pintype "passive"))
      (node (ref "C34") (pin "2") (pinfunction "2_2") (pintype "passive"))
      (node (ref "C35") (pin "-") (pinfunction "-_-") (pintype "passive"))
      (node (ref "C36") (pin "2") (pinfunction "2_2") (pintype "passive"))
      (node (ref "C37") (pin "2") (pinfunction "2_2") (pintype "passive"))
      (node (ref "C38") (pin "-") (pinfunction "-_-") (pintype "passive"))
      (node (ref "C39") (pin "2") (pinfunction "2_2") (pintype "passive"))
      (node (ref "C4") (pin "2") (pinfunction "2_2") (pintype "passive"))
      (node (ref "C40") (pin "-") (pinfunction "-_-") (pintype "passive"))
      (node (ref "C41") (pin "-") (pinfunction "-_-") (pintype "passive"))
      (node (ref "C42") (pin "2") (pinfunction "2_2") (pintype "passive"))
      (node (ref "C43") (pin "2") (pinfunction "2_2") (pintype "passive"))
      (node (ref "C44") (pin "2") (pinfunction "2_2") (pintype "passive"))
      (node (ref "C45") (pin "2") (pinfunction "2_2") (pintype "passive"))
      (node (ref "C46") (pin "2") (pinfunction "2_2") (pintype "passive"))
      (node (ref "C47") (pin "2") (pinfunction "2_2") (pintype "passive"))
      (node (ref "C5") (pin "2") (pinfunction "2_2") (pintype "passive"))
      (node (ref "C50") (pin "1") (pinfunction "1_1") (pintype "passive"))
      (node (ref "C51") (pin "1") (pinfunction "1_1") (pintype "passive"))
      (node (ref "C53") (pin "2") (pinfunction "2_2") (pintype "passive"))
      (node (ref "C54") (pin "2") (pinfunction "2_2") (pintype "passive"))
      (node (ref "C55") (pin "2") (pinfunction "2_2") (pintype "passive"))
      (node (ref "C56") (pin "2") (pinfunction "2_2") (pintype "passive"))
      (node (ref "C57") (pin "2") (pinfunction "2_2") (pintype "passive"))
      (node (ref "C58") (pin "2") (pinfunction "2_2") (pintype "passive"))
      (node (ref "C8") (pin "1") (pinfunction "1_1") (pintype "passive"))
      (node (ref "C9") (pin "2") (pinfunction "2_2") (pintype "passive"))
      (node (ref "D10") (pin "C") (pinfunction "C_C") (pintype "passive"))
      (node (ref "D12") (pin "C") (pinfunction "C_C") (pintype "passive"))
      (node (ref "D13") (pin "C") (pinfunction "C_C") (pintype "passive"))
      (node (ref "D14") (pin "C") (pinfunction "C_C") (pintype "passive"))
      (node (ref "D15") (pin "C") (pinfunction "C_C") (pintype "passive"))
      (node (ref "D18") (pin "C") (pinfunction "C_C") (pintype "passive"))
      (node (ref "D4") (pin "C") (pinfunction "C_C") (pintype "passive"))
      (node (ref "D5") (pin "C") (pinfunction "C_C") (pintype "passive"))
      (node (ref "D6") (pin "C") (pinfunction "C_C") (pintype "passive"))
      (node (ref "D7") (pin "C") (pinfunction "C_C") (pintype "passive"))
      (node (ref "D8") (pin "C") (pinfunction "C_C") (pintype "passive"))
      (node (ref "D9") (pin "C") (pinfunction "C_C") (pintype "passive"))
      (node (ref "J1") (pin "6") (pinfunction "6_6") (pintype "passive"))
      (node (ref "JP15") (pin "1") (pinfunction "1_1") (pintype "passive"))
      (node (ref "JP19") (pin "1") (pinfunction "1_1") (pintype "passive"))
      (node (ref "JP19") (pin "2") (pinfunction "2_2") (pintype "passive"))
      (node (ref "JP2") (pin "11") (pinfunction "11_11") (pintype "passive"))
      (node (ref "JP2") (pin "13") (pinfunction "13_13") (pintype "passive"))
      (node (ref "JP2") (pin "15") (pinfunction "15_15") (pintype "passive"))
      (node (ref "JP2") (pin "17") (pinfunction "17_17") (pintype "passive"))
      (node (ref "JP2") (pin "20") (pinfunction "20_20") (pintype "passive"))
      (node (ref "JP2") (pin "9") (pinfunction "9_9") (pintype "passive"))
      (node (ref "JP5") (pin "GND") (pinfunction "GND_GND") (pintype "bidirectional"))
      (node (ref "JP8") (pin "1") (pinfunction "1_1") (pintype "passive"))
      (node (ref "JP9") (pin "1") (pinfunction "1_1") (pintype "passive"))
      (node (ref "Q1") (pin "2") (pinfunction "2_2") (pintype "passive"))
      (node (ref "Q2") (pin "3") (pinfunction "S_3") (pintype "passive"))
      (node (ref "R1") (pin "1") (pinfunction "1_1") (pintype "passive"))
      (node (ref "R10") (pin "1") (pinfunction "1_1") (pintype "passive"))
      (node (ref "R11") (pin "1") (pinfunction "1_1") (pintype "passive"))
      (node (ref "R12") (pin "1") (pinfunction "1_1") (pintype "passive"))
      (node (ref "R13") (pin "1") (pinfunction "1_1") (pintype "passive"))
      (node (ref "R15") (pin "1") (pinfunction "1_1") (pintype "passive"))
      (node (ref "R17") (pin "1") (pinfunction "1_1") (pintype "passive"))
      (node (ref "R19") (pin "1") (pinfunction "1_1") (pintype "passive"))
      (node (ref "R2") (pin "1") (pinfunction "1_1") (pintype "passive"))
      (node (ref "R20") (pin "1") (pinfunction "1_1") (pintype "passive"))
      (node (ref "R21") (pin "1") (pinfunction "1_1") (pintype "passive"))
      (node (ref "R22") (pin "1") (pinfunction "1_1") (pintype "passive"))
      (node (ref "R24") (pin "1") (pinfunction "1_1") (pintype "passive"))
      (node (ref "R26") (pin "1") (pinfunction "1_1") (pintype "passive"))
      (node (ref "R3") (pin "1") (pinfunction "1_1") (pintype "passive"))
      (node (ref "R4") (pin "1") (pinfunction "1_1") (pintype "passive"))
      (node (ref "R5") (pin "1") (pinfunction "1_1") (pintype "passive"))
      (node (ref "R52") (pin "2") (pinfunction "2_2") (pintype "passive"))
      (node (ref "R54") (pin "1") (pinfunction "1_1") (pintype "passive"))
      (node (ref "R8") (pin "1") (pinfunction "1_1") (pintype "passive"))
      (node (ref "S4") (pin "1") (pinfunction "1_1") (pintype "passive"))
      (node (ref "S5") (pin "3") (pinfunction "3_3") (pintype "bidirectional"))
      (node (ref "S5") (pin "4") (pinfunction "4_4") (pintype "bidirectional"))
      (node (ref "U1") (pin "21") (pinfunction "AGND_21") (pintype "bidirectional"))
      (node (ref "U1") (pin "3") (pinfunction "GND_3") (pintype "bidirectional"))
      (node (ref "U1") (pin "5") (pinfunction "GND_5") (pintype "bidirectional"))
      (node (ref "U10") (pin "3") (pinfunction "GND_3") (pintype "input"))
      (node (ref "U2") (pin "18") (pinfunction "GND18_18") (pintype "power_in"))
      (node (ref "U2") (pin "21") (pinfunction "GND21_21") (pintype "power_in"))
      (node (ref "U2") (pin "25") (pinfunction "AGND_25") (pintype "power_in"))
      (node (ref "U2") (pin "26") (pinfunction "TEST_26") (pintype "input"))
      (node (ref "U2") (pin "7") (pinfunction "GND7_7") (pintype "power_in"))
      (node (ref "U3") (pin "3") (pinfunction "GND_3") (pintype "bidirectional"))
      (node (ref "U4") (pin "5") (pinfunction "SGND_5") (pintype "bidirectional"))
      (node (ref "U4") (pin "7") (pinfunction "CSG_7") (pintype "bidirectional"))
      (node (ref "U4") (pin "PAD") (pinfunction "PAD_GND_PAD") (pintype "bidirectional"))
      (node (ref "U5") (pin "16") (pinfunction "SRN_16") (pintype "bidirectional"))
      (node (ref "U5") (pin "21") (pinfunction "GND_21") (pintype "bidirectional"))
      (node (ref "U5") (pin "7") (pinfunction "GND_7") (pintype "bidirectional"))
      (node (ref "U5") (pin "GND@10") (pinfunction "PAD_GND@10") (pintype "bidirectional"))
      (node (ref "U5") (pin "GND@11") (pinfunction "PAD_GND@11") (pintype "bidirectional"))
      (node (ref "U5") (pin "GND@12") (pinfunction "PAD_GND@12") (pintype "bidirectional"))
      (node (ref "U5") (pin "GND@13") (pinfunction "PAD_GND@13") (pintype "bidirectional"))
      (node (ref "U5") (pin "GND@14") (pinfunction "PAD_GND@14") (pintype "bidirectional"))
      (node (ref "U5") (pin "GND@15") (pinfunction "PAD_GND@15") (pintype "bidirectional"))
      (node (ref "U5") (pin "GND@16") (pinfunction "PAD_GND@16") (pintype "bidirectional"))
      (node (ref "U5") (pin "GND@17") (pinfunction "PAD_GND@17") (pintype "bidirectional"))
      (node (ref "U5") (pin "GND@18") (pinfunction "PAD_GND@18") (pintype "bidirectional"))
      (node (ref "U5") (pin "GND@19") (pinfunction "PAD_GND@19") (pintype "bidirectional"))
      (node (ref "U5") (pin "GND@20") (pinfunction "PAD_GND@20") (pintype "bidirectional"))
      (node (ref "U5") (pin "GND@21") (pinfunction "PAD_GND@21") (pintype "bidirectional"))
      (node (ref "U5") (pin "GND@22") (pinfunction "PAD_GND@22") (pintype "bidirectional"))
      (node (ref "U5") (pin "GND@23") (pinfunction "PAD_GND@23") (pintype "bidirectional"))
      (node (ref "U5") (pin "GND@24") (pinfunction "PAD_GND@24") (pintype "bidirectional"))
      (node (ref "U5") (pin "GND@25") (pinfunction "PAD_GND@25") (pintype "bidirectional"))
      (node (ref "U5") (pin "GND@26") (pinfunction "PAD_GND@26") (pintype "bidirectional"))
      (node (ref "U5") (pin "GND@27") (pinfunction "PAD_GND@27") (pintype "bidirectional"))
      (node (ref "U5") (pin "GND@28") (pinfunction "PAD_GND@28") (pintype "bidirectional"))
      (node (ref "U5") (pin "GND@29") (pinfunction "PAD_GND@29") (pintype "bidirectional"))
      (node (ref "U5") (pin "GND@30") (pinfunction "PAD_GND@30") (pintype "bidirectional"))
      (node (ref "U5") (pin "GND@PAD") (pinfunction "PAD_GND@PAD") (pintype "bidirectional"))
      (node (ref "U6") (pin "13") (pinfunction "6A_13") (pintype "input"))
      (node (ref "U6") (pin "7") (pinfunction "GND_7") (pintype "power_in"))
      (node (ref "U7") (pin "3") (pinfunction "GND_3") (pintype "bidirectional"))
      (node (ref "U8") (pin "16") (pinfunction "SRN_16") (pintype "bidirectional"))
      (node (ref "U8") (pin "21") (pinfunction "GND_21") (pintype "bidirectional"))
      (node (ref "U8") (pin "7") (pinfunction "GND_7") (pintype "bidirectional"))
      (node (ref "U8") (pin "GND@10") (pinfunction "PAD_GND@10") (pintype "bidirectional"))
      (node (ref "U8") (pin "GND@11") (pinfunction "PAD_GND@11") (pintype "bidirectional"))
      (node (ref "U8") (pin "GND@12") (pinfunction "PAD_GND@12") (pintype "bidirectional"))
      (node (ref "U8") (pin "GND@13") (pinfunction "PAD_GND@13") (pintype "bidirectional"))
      (node (ref "U8") (pin "GND@14") (pinfunction "PAD_GND@14") (pintype "bidirectional"))
      (node (ref "U8") (pin "GND@15") (pinfunction "PAD_GND@15") (pintype "bidirectional"))
      (node (ref "U8") (pin "GND@16") (pinfunction "PAD_GND@16") (pintype "bidirectional"))
      (node (ref "U8") (pin "GND@17") (pinfunction "PAD_GND@17") (pintype "bidirectional"))
      (node (ref "U8") (pin "GND@18") (pinfunction "PAD_GND@18") (pintype "bidirectional"))
      (node (ref "U8") (pin "GND@19") (pinfunction "PAD_GND@19") (pintype "bidirectional"))
      (node (ref "U8") (pin "GND@20") (pinfunction "PAD_GND@20") (pintype "bidirectional"))
      (node (ref "U8") (pin "GND@21") (pinfunction "PAD_GND@21") (pintype "bidirectional"))
      (node (ref "U8") (pin "GND@22") (pinfunction "PAD_GND@22") (pintype "bidirectional"))
      (node (ref "U8") (pin "GND@23") (pinfunction "PAD_GND@23") (pintype "bidirectional"))
      (node (ref "U8") (pin "GND@24") (pinfunction "PAD_GND@24") (pintype "bidirectional"))
      (node (ref "U8") (pin "GND@25") (pinfunction "PAD_GND@25") (pintype "bidirectional"))
      (node (ref "U8") (pin "GND@26") (pinfunction "PAD_GND@26") (pintype "bidirectional"))
      (node (ref "U8") (pin "GND@27") (pinfunction "PAD_GND@27") (pintype "bidirectional"))
      (node (ref "U8") (pin "GND@28") (pinfunction "PAD_GND@28") (pintype "bidirectional"))
      (node (ref "U8") (pin "GND@29") (pinfunction "PAD_GND@29") (pintype "bidirectional"))
      (node (ref "U8") (pin "GND@30") (pinfunction "PAD_GND@30") (pintype "bidirectional"))
      (node (ref "U8") (pin "GND@PAD") (pinfunction "PAD_GND@PAD") (pintype "bidirectional"))
      (node (ref "U9") (pin "16") (pinfunction "SRN_16") (pintype "bidirectional"))
      (node (ref "U9") (pin "21") (pinfunction "GND_21") (pintype "bidirectional"))
      (node (ref "U9") (pin "7") (pinfunction "GND_7") (pintype "bidirectional"))
      (node (ref "U9") (pin "GND@10") (pinfunction "PAD_GND@10") (pintype "bidirectional"))
      (node (ref "U9") (pin "GND@11") (pinfunction "PAD_GND@11") (pintype "bidirectional"))
      (node (ref "U9") (pin "GND@12") (pinfunction "PAD_GND@12") (pintype "bidirectional"))
      (node (ref "U9") (pin "GND@13") (pinfunction "PAD_GND@13") (pintype "bidirectional"))
      (node (ref "U9") (pin "GND@14") (pinfunction "PAD_GND@14") (pintype "bidirectional"))
      (node (ref "U9") (pin "GND@15") (pinfunction "PAD_GND@15") (pintype "bidirectional"))
      (node (ref "U9") (pin "GND@16") (pinfunction "PAD_GND@16") (pintype "bidirectional"))
      (node (ref "U9") (pin "GND@17") (pinfunction "PAD_GND@17") (pintype "bidirectional"))
      (node (ref "U9") (pin "GND@18") (pinfunction "PAD_GND@18") (pintype "bidirectional"))
      (node (ref "U9") (pin "GND@19") (pinfunction "PAD_GND@19") (pintype "bidirectional"))
      (node (ref "U9") (pin "GND@20") (pinfunction "PAD_GND@20") (pintype "bidirectional"))
      (node (ref "U9") (pin "GND@21") (pinfunction "PAD_GND@21") (pintype "bidirectional"))
      (node (ref "U9") (pin "GND@22") (pinfunction "PAD_GND@22") (pintype "bidirectional"))
      (node (ref "U9") (pin "GND@23") (pinfunction "PAD_GND@23") (pintype "bidirectional"))
      (node (ref "U9") (pin "GND@24") (pinfunction "PAD_GND@24") (pintype "bidirectional"))
      (node (ref "U9") (pin "GND@25") (pinfunction "PAD_GND@25") (pintype "bidirectional"))
      (node (ref "U9") (pin "GND@26") (pinfunction "PAD_GND@26") (pintype "bidirectional"))
      (node (ref "U9") (pin "GND@27") (pinfunction "PAD_GND@27") (pintype "bidirectional"))
      (node (ref "U9") (pin "GND@28") (pinfunction "PAD_GND@28") (pintype "bidirectional"))
      (node (ref "U9") (pin "GND@29") (pinfunction "PAD_GND@29") (pintype "bidirectional"))
      (node (ref "U9") (pin "GND@30") (pinfunction "PAD_GND@30") (pintype "bidirectional"))
      (node (ref "U9") (pin "GND@PAD") (pinfunction "PAD_GND@PAD") (pintype "bidirectional"))
    )
    (net (code "24") (name "MISO-D12-LIMIT-Z") (class "Default")
      (node (ref "J1") (pin "1") (pinfunction "1_1") (pintype "passive"))
      (node (ref "R45") (pin "2") (pinfunction "2_2") (pintype "passive"))
      (node (ref "U1") (pin "16") (pinfunction "PB4(MISO)_16") (pintype "bidirectional"))
      (node (ref "U6") (pin "6") (pinfunction "3Y_6") (pintype "output"))
    )
    (net (code "25") (name "MOSI-D11-SPINDLE_PWM") (class "Default")
      (node (ref "J1") (pin "4") (pinfunction "4_4") (pintype "passive"))
      (node (ref "JP2") (pin "26") (pinfunction "26_26") (pintype "passive"))
      (node (ref "U1") (pin "15") (pinfunction "PB3(MOSI/OC2)_15") (pintype "bidirectional"))
    )
    (net (code "26") (name "Net-(D1-PadA)") (class "Default")
      (node (ref "D1") (pin "A") (pinfunction "A_A") (pintype "passive"))
      (node (ref "R18") (pin "1") (pinfunction "1_1") (pintype "passive"))
    )
    (net (code "27") (name "Net-(D2-PadA)") (class "Default")
      (node (ref "D2") (pin "A") (pinfunction "A_A") (pintype "passive"))
      (node (ref "R9") (pin "1") (pinfunction "1_1") (pintype "passive"))
    )
    (net (code "28") (name "Net-(D3-PadC)") (class "Default")
      (node (ref "D3") (pin "C") (pinfunction "C_C") (pintype "passive"))
      (node (ref "R51") (pin "2") (pinfunction "2_2") (pintype "passive"))
    )
    (net (code "29") (name "Net-(D4-PadA)") (class "Default")
      (node (ref "D4") (pin "A") (pinfunction "A_A") (pintype "passive"))
      (node (ref "R39") (pin "1") (pinfunction "1_1") (pintype "passive"))
    )
    (net (code "30") (name "Net-(D5-PadA)") (class "Default")
      (node (ref "D5") (pin "A") (pinfunction "A_A") (pintype "passive"))
      (node (ref "R32") (pin "1") (pinfunction "1_1") (pintype "passive"))
    )
    (net (code "31") (name "Net-(D6-PadA)") (class "Default")
      (node (ref "D6") (pin "A") (pinfunction "A_A") (pintype "passive"))
      (node (ref "R31") (pin "1") (pinfunction "1_1") (pintype "passive"))
    )
    (net (code "32") (name "Net-(D7-PadA)") (class "Default")
      (node (ref "D7") (pin "A") (pinfunction "A_A") (pintype "passive"))
      (node (ref "R40") (pin "1") (pinfunction "1_1") (pintype "passive"))
    )
    (net (code "33") (name "Net-(D8-PadA)") (class "Default")
      (node (ref "D8") (pin "A") (pinfunction "A_A") (pintype "passive"))
      (node (ref "R43") (pin "1") (pinfunction "1_1") (pintype "passive"))
    )
    (net (code "34") (name "Net-(D9-PadA)") (class "Default")
      (node (ref "D9") (pin "A") (pinfunction "A_A") (pintype "passive"))
      (node (ref "R42") (pin "1") (pinfunction "1_1") (pintype "passive"))
    )
    (net (code "35") (name "Net-(D10-PadA)") (class "Default")
      (node (ref "D10") (pin "A") (pinfunction "A_A") (pintype "passive"))
      (node (ref "R41") (pin "1") (pinfunction "1_1") (pintype "passive"))
    )
    (net (code "36") (name "Net-(D11-PadA)") (class "Default")
      (node (ref "D11") (pin "A") (pinfunction "A_A") (pintype "passive"))
      (node (ref "R44") (pin "1") (pinfunction "1_1") (pintype "passive"))
    )
    (net (code "37") (name "Net-(D12-PadA)") (class "Default")
      (node (ref "D12") (pin "A") (pinfunction "A_A") (pintype "passive"))
      (node (ref "R47") (pin "1") (pinfunction "1_1") (pintype "passive"))
    )
    (net (code "38") (name "Net-(D13-PadA)") (class "Default")
      (node (ref "D13") (pin "A") (pinfunction "A_A") (pintype "passive"))
      (node (ref "R46") (pin "1") (pinfunction "1_1") (pintype "passive"))
    )
    (net (code "39") (name "Net-(D14-PadA)") (class "Default")
      (node (ref "D14") (pin "A") (pinfunction "A_A") (pintype "passive"))
      (node (ref "R45") (pin "1") (pinfunction "1_1") (pintype "passive"))
    )
    (net (code "40") (name "Net-(D15-PadA)") (class "Default")
      (node (ref "D15") (pin "A") (pinfunction "A_A") (pintype "passive"))
      (node (ref "R49") (pin "1") (pinfunction "1_1") (pintype "passive"))
    )
    (net (code "41") (name "Net-(D16-PadA)") (class "Default")
      (node (ref "D16") (pin "A") (pinfunction "A_A") (pintype "passive"))
      (node (ref "F1") (pin "2") (pinfunction "2_2") (pintype "bidirectional"))
    )
    (net (code "42") (name "Net-(D18-PadA)") (class "Default")
      (node (ref "D18") (pin "A") (pinfunction "A_A") (pintype "passive"))
      (node (ref "R56") (pin "2") (pinfunction "2_2") (pintype "passive"))
    )
    (net (code "43") (name "Net-(JP1-Pad1)") (class "Default")
      (node (ref "JP1") (pin "1") (pinfunction "1_1") (pintype "passive"))
      (node (ref "JP3") (pin "1") (pinfunction "1_1") (pintype "passive"))
      (node (ref "JP4") (pin "1") (pinfunction "1_1") (pintype "passive"))
      (node (ref "S5") (pin "5") (pinfunction "5_5") (pintype "bidirectional"))
    )
    (net (code "44") (name "Net-(JP1-Pad2)") (class "Default")
      (node (ref "JP1") (pin "2") (pinfunction "2_2") (pintype "passive"))
      (node (ref "R30") (pin "1") (pinfunction "1_1") (pintype "passive"))
      (node (ref "R38") (pin "2") (pinfunction "2_2") (pintype "passive"))
    )
    (net (code "45") (name "Net-(JP3-Pad2)") (class "Default")
      (node (ref "JP3") (pin "2") (pinfunction "2_2") (pintype "passive"))
      (node (ref "R27") (pin "2") (pinfunction "2_2") (pintype "passive"))
      (node (ref "R33") (pin "1") (pinfunction "1_1") (pintype "passive"))
    )
    (net (code "46") (name "Net-(JP4-Pad2)") (class "Default")
      (node (ref "JP4") (pin "2") (pinfunction "2_2") (pintype "passive"))
      (node (ref "R28") (pin "2") (pinfunction "2_2") (pintype "passive"))
      (node (ref "R34") (pin "1") (pinfunction "1_1") (pintype "passive"))
    )
    (net (code "47") (name "Net-(JP8-Pad2)") (class "Default")
      (node (ref "JP8") (pin "2") (pinfunction "2_2") (pintype "passive"))
      (node (ref "R29") (pin "2") (pinfunction "2_2") (pintype "passive"))
      (node (ref "R36") (pin "1") (pinfunction "1_1") (pintype "passive"))
    )
    (net (code "48") (name "Net-(JP9-Pad2)") (class "Default")
      (node (ref "JP9") (pin "2") (pinfunction "2_2") (pintype "passive"))
      (node (ref "R35") (pin "2") (pinfunction "2_2") (pintype "passive"))
      (node (ref "R48") (pin "1") (pinfunction "1_1") (pintype "passive"))
    )
    (net (code "49") (name "Net-(L1-1)") (class "Default")
      (node (ref "C7") (pin "2") (pinfunction "2_2") (pintype "passive"))
      (node (ref "D17") (pin "C") (pinfunction "C_C") (pintype "passive"))
      (node (ref "L1") (pin "P$1") (pinfunction "1_P$1") (pintype "passive"))
      (node (ref "U4") (pin "9") (pinfunction "SW_9") (pintype "bidirectional"))
    )
    (net (code "50") (name "Net-(POT1-A)") (class "Default")
      (node (ref "POT1") (pin "1") (pinfunction "A_1") (pintype "passive"))
      (node (ref "R1") (pin "2") (pinfunction "2_2") (pintype "passive"))
    )
    (net (code "51") (name "Net-(POT1-E)") (class "Default")
      (node (ref "POT1") (pin "3") (pinfunction "E_3") (pintype "passive"))
      (node (ref "R37") (pin "1") (pinfunction "1_1") (pintype "passive"))
    )
    (net (code "52") (name "Net-(POT1-S)") (class "Default")
      (node (ref "POT1") (pin "2") (pinfunction "S_2") (pintype "passive"))
      (node (ref "U5") (pin "8") (pinfunction "VREF_8") (pintype "bidirectional"))
    )
    (net (code "53") (name "Net-(POT2-A)") (class "Default")
      (node (ref "POT2") (pin "1") (pinfunction "A_1") (pintype "passive"))
      (node (ref "R17") (pin "2") (pinfunction "2_2") (pintype "passive"))
    )
    (net (code "54") (name "Net-(POT2-E)") (class "Default")
      (node (ref "POT2") (pin "3") (pinfunction "E_3") (pintype "passive"))
      (node (ref "R16") (pin "1") (pinfunction "1_1") (pintype "passive"))
    )
    (net (code "55") (name "Net-(POT2-S)") (class "Default")
      (node (ref "POT2") (pin "2") (pinfunction "S_2") (pintype "passive"))
      (node (ref "U8") (pin "8") (pinfunction "VREF_8") (pintype "bidirectional"))
    )
    (net (code "56") (name "Net-(POT3-A)") (class "Default")
      (node (ref "POT3") (pin "1") (pinfunction "A_1") (pintype "passive"))
      (node (ref "R26") (pin "2") (pinfunction "2_2") (pintype "passive"))
    )
    (net (code "57") (name "Net-(POT3-E)") (class "Default")
      (node (ref "POT3") (pin "3") (pinfunction "E_3") (pintype "passive"))
      (node (ref "R25") (pin "1") (pinfunction "1_1") (pintype "passive"))
    )
    (net (code "58") (name "Net-(POT3-S)") (class "Default")
      (node (ref "POT3") (pin "2") (pinfunction "S_2") (pintype "passive"))
      (node (ref "U9") (pin "8") (pinfunction "VREF_8") (pintype "bidirectional"))
    )
    (net (code "59") (name "Net-(Q2-D)") (class "Default")
      (node (ref "C2") (pin "1") (pinfunction "1_1") (pintype "passive"))
      (node (ref "D3") (pin "A") (pinfunction "A_A") (pintype "passive"))
      (node (ref "JP6") (pin "GND") (pinfunction "GND_GND") (pintype "bidirectional"))
      (node (ref "Q2") (pin "2") (pinfunction "D_2") (pintype "passive"))
      (node (ref "VIN") (pin "1") (pinfunction "1_1") (pintype "passive"))
    )
    (net (code "60") (name "Net-(Q2-G)") (class "Default")
      (node (ref "Q2") (pin "1") (pinfunction "G_1") (pintype "passive"))
      (node (ref "R50") (pin "2") (pinfunction "2_2") (pintype "passive"))
    )
    (net (code "61") (name "Net-(R27-Pad1)") (class "Default")
      (node (ref "R27") (pin "1") (pinfunction "1_1") (pintype "passive"))
      (node (ref "R28") (pin "1") (pinfunction "1_1") (pintype "passive"))
      (node (ref "R38") (pin "1") (pinfunction "1_1") (pintype "passive"))
      (node (ref "S5") (pin "2") (pinfunction "2_2") (pintype "bidirectional"))
    )
    (net (code "62") (name "Net-(S1-P$1)") (class "Default")
      (node (ref "S1") (pin "1") (pinfunction "P$1_1") (pintype "bidirectional"))
      (node (ref "U5") (pin "12") (pinfunction "USM1_12") (pintype "bidirectional"))
    )
    (net (code "63") (name "Net-(S1-P$2)") (class "Default")
      (node (ref "S1") (pin "2") (pinfunction "P$2_2") (pintype "bidirectional"))
      (node (ref "U5") (pin "13") (pinfunction "USM0_13") (pintype "bidirectional"))
    )
    (net (code "64") (name "Net-(S2-P$1)") (class "Default")
      (node (ref "S2") (pin "1") (pinfunction "P$1_1") (pintype "bidirectional"))
      (node (ref "U8") (pin "12") (pinfunction "USM1_12") (pintype "bidirectional"))
    )
    (net (code "65") (name "Net-(S2-P$2)") (class "Default")
      (node (ref "S2") (pin "2") (pinfunction "P$2_2") (pintype "bidirectional"))
      (node (ref "U8") (pin "13") (pinfunction "USM0_13") (pintype "bidirectional"))
    )
    (net (code "66") (name "Net-(S3-P$1)") (class "Default")
      (node (ref "S3") (pin "1") (pinfunction "P$1_1") (pintype "bidirectional"))
      (node (ref "U9") (pin "12") (pinfunction "USM1_12") (pintype "bidirectional"))
    )
    (net (code "67") (name "Net-(S3-P$2)") (class "Default")
      (node (ref "S3") (pin "2") (pinfunction "P$2_2") (pintype "bidirectional"))
      (node (ref "U9") (pin "13") (pinfunction "USM0_13") (pintype "bidirectional"))
    )
    (net (code "68") (name "Net-(U1-PB6(XTAL1{slash}TOSC1))") (class "Default")
      (node (ref "Q1") (pin "1") (pinfunction "1_1") (pintype "passive"))
      (node (ref "U1") (pin "7") (pinfunction "PB6(XTAL1/TOSC1)_7") (pintype "bidirectional"))
    )
    (net (code "69") (name "Net-(U1-PB7(XTAL2{slash}TOSC2))") (class "Default")
      (node (ref "Q1") (pin "3") (pinfunction "3_3") (pintype "passive"))
      (node (ref "U1") (pin "8") (pinfunction "PB7(XTAL2/TOSC2)_8") (pintype "bidirectional"))
    )
    (net (code "70") (name "Net-(U2-3V3OUT)") (class "Default")
      (node (ref "C47") (pin "1") (pinfunction "1_1") (pintype "passive"))
      (node (ref "U2") (pin "17") (pinfunction "3V3OUT_17") (pintype "output"))
    )
    (net (code "71") (name "Net-(U2-RXD)") (class "Default")
      (node (ref "R57") (pin "2") (pinfunction "2_2") (pintype "passive"))
      (node (ref "U2") (pin "5") (pinfunction "RXD_5") (pintype "input"))
    )
    (net (code "72") (name "Net-(U2-RXLED)") (class "Default")
      (node (ref "D2") (pin "C") (pinfunction "C_C") (pintype "passive"))
      (node (ref "U2") (pin "22") (pinfunction "RXLED_22") (pintype "input"))
    )
    (net (code "73") (name "Net-(U2-TXD)") (class "Default")
      (node (ref "R58") (pin "2") (pinfunction "2_2") (pintype "passive"))
      (node (ref "U2") (pin "1") (pinfunction "TXD_1") (pintype "output"))
    )
    (net (code "74") (name "Net-(U2-TXLED)") (class "Default")
      (node (ref "D1") (pin "C") (pinfunction "C_C") (pintype "passive"))
      (node (ref "U2") (pin "23") (pinfunction "TXLED_23") (pintype "input"))
    )
    (net (code "75") (name "Net-(U2-USBDM)") (class "Default")
      (node (ref "JP5") (pin "D-") (pinfunction "D-_D-") (pintype "bidirectional"))
      (node (ref "U2") (pin "16") (pinfunction "USBDM_16") (pintype "bidirectional"))
    )
    (net (code "76") (name "Net-(U2-USBDP)") (class "Default")
      (node (ref "JP5") (pin "D+") (pinfunction "D+_D+") (pintype "bidirectional"))
      (node (ref "U2") (pin "15") (pinfunction "USBDP_15") (pintype "bidirectional"))
    )
    (net (code "77") (name "Net-(U4-BST)") (class "Default")
      (node (ref "C7") (pin "1") (pinfunction "1_1") (pintype "passive"))
      (node (ref "U4") (pin "10") (pinfunction "BST_10") (pintype "bidirectional"))
    )
    (net (code "78") (name "Net-(U4-CS)") (class "Default")
      (node (ref "D17") (pin "A") (pinfunction "A_A") (pintype "passive"))
      (node (ref "R54") (pin "2") (pinfunction "2_2") (pintype "passive"))
      (node (ref "U4") (pin "8") (pinfunction "CS_8") (pintype "bidirectional"))
    )
    (net (code "79") (name "Net-(U4-FB)") (class "Default")
      (node (ref "R52") (pin "1") (pinfunction "1_1") (pintype "passive"))
      (node (ref "R53") (pin "1") (pinfunction "1_1") (pintype "passive"))
      (node (ref "U4") (pin "6") (pinfunction "FB_6") (pintype "bidirectional"))
    )
    (net (code "80") (name "Net-(U4-RT)") (class "Default")
      (node (ref "R55") (pin "1") (pinfunction "1_1") (pintype "passive"))
      (node (ref "U4") (pin "2") (pinfunction "RT_2") (pintype "bidirectional"))
    )
    (net (code "81") (name "Net-(U4-SS)") (class "Default")
      (node (ref "C9") (pin "1") (pinfunction "1_1") (pintype "passive"))
      (node (ref "U4") (pin "4") (pinfunction "SS_4") (pintype "bidirectional"))
    )
    (net (code "82") (name "Net-(U5-AOUT1)") (class "Default")
      (node (ref "U5") (pin "4") (pinfunction "AOUT1_4") (pintype "bidirectional"))
      (node (ref "X-A") (pin "1") (pinfunction "1_1") (pintype "passive"))
    )
    (net (code "83") (name "Net-(U5-AOUT2)") (class "Default")
      (node (ref "U5") (pin "25") (pinfunction "AOUT2_25") (pintype "bidirectional"))
      (node (ref "X-A") (pin "2") (pinfunction "2_2") (pintype "passive"))
    )
    (net (code "84") (name "Net-(U5-BOUT1)") (class "Default")
      (node (ref "U5") (pin "11") (pinfunction "BOUT1_11") (pintype "bidirectional"))
      (node (ref "X-B") (pin "1") (pinfunction "1_1") (pintype "passive"))
    )
    (net (code "85") (name "Net-(U5-BOUT2)") (class "Default")
      (node (ref "U5") (pin "18") (pinfunction "BOUT2_18") (pintype "bidirectional"))
      (node (ref "X-B") (pin "2") (pinfunction "2_2") (pintype "passive"))
    )
    (net (code "86") (name "Net-(U5-CP1)") (class "Default")
      (node (ref "C16") (pin "2") (pinfunction "2_2") (pintype "passive"))
      (node (ref "U5") (pin "23") (pinfunction "CP1_23") (pintype "bidirectional"))
    )
    (net (code "87") (name "Net-(U5-CP2)") (class "Default")
      (node (ref "C16") (pin "1") (pinfunction "1_1") (pintype "passive"))
      (node (ref "U5") (pin "24") (pinfunction "CP2_24") (pintype "bidirectional"))
    )
    (net (code "88") (name "Net-(U5-DECAY)") (class "Default")
      (node (ref "C32") (pin "1") (pinfunction "1_1") (pintype "passive"))
      (node (ref "R14") (pin "1") (pinfunction "1_1") (pintype "passive"))
      (node (ref "R15") (pin "2") (pinfunction "2_2") (pintype "passive"))
      (node (ref "U5") (pin "5") (pinfunction "DECAY_5") (pintype "bidirectional"))
    )
    (net (code "89") (name "Net-(U5-ISENA)") (class "Default")
      (node (ref "C20") (pin "1") (pinfunction "1_1") (pintype "passive"))
      (node (ref "R10") (pin "2") (pinfunction "2_2") (pintype "passive"))
      (node (ref "U5") (pin "1") (pinfunction "ISENA_1") (pintype "bidirectional"))
    )
    (net (code "90") (name "Net-(U5-ISENB)") (class "Default")
      (node (ref "C19") (pin "1") (pinfunction "1_1") (pintype "passive"))
      (node (ref "R11") (pin "2") (pinfunction "2_2") (pintype "passive"))
      (node (ref "U5") (pin "14") (pinfunction "ISENB_14") (pintype "bidirectional"))
    )
    (net (code "91") (name "Net-(U5-RCA)") (class "Default")
      (node (ref "C21") (pin "1") (pinfunction "1_1") (pintype "passive"))
      (node (ref "R12") (pin "2") (pinfunction "2_2") (pintype "passive"))
      (node (ref "U5") (pin "6") (pinfunction "RCA_6") (pintype "bidirectional"))
    )
    (net (code "92") (name "Net-(U5-RCB)") (class "Default")
      (node (ref "C22") (pin "1") (pinfunction "1_1") (pintype "passive"))
      (node (ref "R13") (pin "2") (pinfunction "2_2") (pintype "passive"))
      (node (ref "U5") (pin "9") (pinfunction "RCB_9") (pintype "bidirectional"))
    )
    (net (code "93") (name "Net-(U5-VCP)") (class "Default")
      (node (ref "C17") (pin "2") (pinfunction "2_2") (pintype "passive"))
      (node (ref "U5") (pin "22") (pinfunction "VCP_22") (pintype "bidirectional"))
    )
    (net (code "94") (name "Net-(U5-VGD)") (class "Default")
      (node (ref "C18") (pin "2") (pinfunction "2_2") (pintype "passive"))
      (node (ref "U5") (pin "20") (pinfunction "VGD_20") (pintype "bidirectional"))
    )
    (net (code "95") (name "Net-(U8-AOUT1)") (class "Default")
      (node (ref "U8") (pin "4") (pinfunction "AOUT1_4") (pintype "bidirectional"))
      (node (ref "Y-A") (pin "1") (pinfunction "1_1") (pintype "passive"))
    )
    (net (code "96") (name "Net-(U8-AOUT2)") (class "Default")
      (node (ref "U8") (pin "25") (pinfunction "AOUT2_25") (pintype "bidirectional"))
      (node (ref "Y-A") (pin "2") (pinfunction "2_2") (pintype "passive"))
    )
    (net (code "97") (name "Net-(U8-BOUT1)") (class "Default")
      (node (ref "U8") (pin "11") (pinfunction "BOUT1_11") (pintype "bidirectional"))
      (node (ref "Y-B") (pin "1") (pinfunction "1_1") (pintype "passive"))
    )
    (net (code "98") (name "Net-(U8-BOUT2)") (class "Default")
      (node (ref "U8") (pin "18") (pinfunction "BOUT2_18") (pintype "bidirectional"))
      (node (ref "Y-B") (pin "2") (pinfunction "2_2") (pintype "passive"))
    )
    (net (code "99") (name "Net-(U8-CP1)") (class "Default")
      (node (ref "C1") (pin "2") (pinfunction "2_2") (pintype "passive"))
      (node (ref "U8") (pin "23") (pinfunction "CP1_23") (pintype "bidirectional"))
    )
    (net (code "100") (name "Net-(U8-CP2)") (class "Default")
      (node (ref "C1") (pin "1") (pinfunction "1_1") (pintype "passive"))
      (node (ref "U8") (pin "24") (pinfunction "CP2_24") (pintype "bidirectional"))
    )
    (net (code "101") (name "Net-(U8-DECAY)") (class "Default")
      (node (ref "C15") (pin "1") (pinfunction "1_1") (pintype "passive"))
      (node (ref "R7") (pin "1") (pinfunction "1_1") (pintype "passive"))
      (node (ref "R8") (pin "2") (pinfunction "2_2") (pintype "passive"))
      (node (ref "U8") (pin "5") (pinfunction "DECAY_5") (pintype "bidirectional"))
    )
    (net (code "102") (name "Net-(U8-ISENA)") (class "Default")
      (node (ref "C11") (pin "1") (pinfunction "1_1") (pintype "passive"))
      (node (ref "R2") (pin "2") (pinfunction "2_2") (pintype "passive"))
      (node (ref "U8") (pin "1") (pinfunction "ISENA_1") (pintype "bidirectional"))
    )
    (net (code "103") (name "Net-(U8-ISENB)") (class "Default")
      (node (ref "C10") (pin "1") (pinfunction "1_1") (pintype "passive"))
      (node (ref "R3") (pin "2") (pinfunction "2_2") (pintype "passive"))
      (node (ref "U8") (pin "14") (pinfunction "ISENB_14") (pintype "bidirectional"))
    )
    (net (code "104") (name "Net-(U8-RCA)") (class "Default")
      (node (ref "C12") (pin "1") (pinfunction "1_1") (pintype "passive"))
      (node (ref "R4") (pin "2") (pinfunction "2_2") (pintype "passive"))
      (node (ref "U8") (pin "6") (pinfunction "RCA_6") (pintype "bidirectional"))
    )
    (net (code "105") (name "Net-(U8-RCB)") (class "Default")
      (node (ref "C13") (pin "1") (pinfunction "1_1") (pintype "passive"))
      (node (ref "R5") (pin "2") (pinfunction "2_2") (pintype "passive"))
      (node (ref "U8") (pin "9") (pinfunction "RCB_9") (pintype "bidirectional"))
    )
    (net (code "106") (name "Net-(U8-VCP)") (class "Default")
      (node (ref "C6") (pin "2") (pinfunction "2_2") (pintype "passive"))
      (node (ref "U8") (pin "22") (pinfunction "VCP_22") (pintype "bidirectional"))
    )
    (net (code "107") (name "Net-(U8-VGD)") (class "Default")
      (node (ref "C8") (pin "2") (pinfunction "2_2") (pintype "passive"))
      (node (ref "U8") (pin "20") (pinfunction "VGD_20") (pintype "bidirectional"))
    )
    (net (code "108") (name "Net-(U9-AOUT1)") (class "Default")
      (node (ref "U9") (pin "4") (pinfunction "AOUT1_4") (pintype "bidirectional"))
      (node (ref "Z-A") (pin "1") (pinfunction "1_1") (pintype "passive"))
    )
    (net (code "109") (name "Net-(U9-AOUT2)") (class "Default")
      (node (ref "U9") (pin "25") (pinfunction "AOUT2_25") (pintype "bidirectional"))
      (node (ref "Z-A") (pin "2") (pinfunction "2_2") (pintype "passive"))
    )
    (net (code "110") (name "Net-(U9-BOUT1)") (class "Default")
      (node (ref "U9") (pin "11") (pinfunction "BOUT1_11") (pintype "bidirectional"))
      (node (ref "Z-B") (pin "1") (pinfunction "1_1") (pintype "passive"))
    )
    (net (code "111") (name "Net-(U9-BOUT2)") (class "Default")
      (node (ref "U9") (pin "18") (pinfunction "BOUT2_18") (pintype "bidirectional"))
      (node (ref "Z-B") (pin "2") (pinfunction "2_2") (pintype "passive"))
    )
    (net (code "112") (name "Net-(U9-CP1)") (class "Default")
      (node (ref "C27") (pin "2") (pinfunction "2_2") (pintype "passive"))
      (node (ref "U9") (pin "23") (pinfunction "CP1_23") (pintype "bidirectional"))
    )
    (net (code "113") (name "Net-(U9-CP2)") (class "Default")
      (node (ref "C27") (pin "1") (pinfunction "1_1") (pintype "passive"))
      (node (ref "U9") (pin "24") (pinfunction "CP2_24") (pintype "bidirectional"))
    )
    (net (code "114") (name "Net-(U9-DECAY)") (class "Default")
      (node (ref "C36") (pin "1") (pinfunction "1_1") (pintype "passive"))
      (node (ref "R23") (pin "1") (pinfunction "1_1") (pintype "passive"))
      (node (ref "R24") (pin "2") (pinfunction "2_2") (pintype "passive"))
      (node (ref "U9") (pin "5") (pinfunction "DECAY_5") (pintype "bidirectional"))
    )
    (net (code "115") (name "Net-(U9-ISENA)") (class "Default")
      (node (ref "C31") (pin "1") (pinfunction "1_1") (pintype "passive"))
      (node (ref "R19") (pin "2") (pinfunction "2_2") (pintype "passive"))
      (node (ref "U9") (pin "1") (pinfunction "ISENA_1") (pintype "bidirectional"))
    )
    (net (code "116") (name "Net-(U9-ISENB)") (class "Default")
      (node (ref "C30") (pin "1") (pinfunction "1_1") (pintype "passive"))
      (node (ref "R20") (pin "2") (pinfunction "2_2") (pintype "passive"))
      (node (ref "U9") (pin "14") (pinfunction "ISENB_14") (pintype "bidirectional"))
    )
    (net (code "117") (name "Net-(U9-RCA)") (class "Default")
      (node (ref "C33") (pin "1") (pinfunction "1_1") (pintype "passive"))
      (node (ref "R21") (pin "2") (pinfunction "2_2") (pintype "passive"))
      (node (ref "U9") (pin "6") (pinfunction "RCA_6") (pintype "bidirectional"))
    )
    (net (code "118") (name "Net-(U9-RCB)") (class "Default")
      (node (ref "C34") (pin "1") (pinfunction "1_1") (pintype "passive"))
      (node (ref "R22") (pin "2") (pinfunction "2_2") (pintype "passive"))
      (node (ref "U9") (pin "9") (pinfunction "RCB_9") (pintype "bidirectional"))
    )
    (net (code "119") (name "Net-(U9-VCP)") (class "Default")
      (node (ref "C28") (pin "2") (pinfunction "2_2") (pintype "passive"))
      (node (ref "U9") (pin "22") (pinfunction "VCP_22") (pintype "bidirectional"))
    )
    (net (code "120") (name "Net-(U9-VGD)") (class "Default")
      (node (ref "C29") (pin "2") (pinfunction "2_2") (pintype "passive"))
      (node (ref "U9") (pin "20") (pinfunction "VGD_20") (pintype "bidirectional"))
    )
    (net (code "121") (name "PROBE") (class "Default")
      (node (ref "C57") (pin "1") (pinfunction "1_1") (pintype "passive"))
      (node (ref "D11") (pin "C") (pinfunction "C_C") (pintype "passive"))
      (node (ref "R36") (pin "2") (pinfunction "2_2") (pintype "passive"))
      (node (ref "U6") (pin "9") (pinfunction "4A_9") (pintype "input"))
    )
    (net (code "122") (name "RESET") (class "Default")
      (node (ref "C52") (pin "1") (pinfunction "1_1") (pintype "passive"))
      (node (ref "J1") (pin "5") (pinfunction "5_5") (pintype "passive"))
      (node (ref "JP2") (pin "18") (pinfunction "18_18") (pintype "passive"))
      (node (ref "R6") (pin "1") (pinfunction "1_1") (pintype "passive"))
      (node (ref "S4") (pin "3") (pinfunction "2_3") (pintype "passive"))
      (node (ref "U1") (pin "29") (pinfunction "PC6(/RESET)_29") (pintype "bidirectional"))
    )
    (net (code "123") (name "RXI") (class "Default")
      (node (ref "JP2") (pin "21") (pinfunction "21_21") (pintype "passive"))
      (node (ref "R58") (pin "1") (pinfunction "1_1") (pintype "passive"))
      (node (ref "U1") (pin "30") (pinfunction "PD0(RXD)_30") (pintype "bidirectional"))
    )
    (net (code "124") (name "SCK-D13-SPINDLE_DIR") (class "Default")
      (node (ref "J1") (pin "3") (pinfunction "3_3") (pintype "passive"))
      (node (ref "JP2") (pin "25") (pinfunction "25_25") (pintype "passive"))
      (node (ref "U1") (pin "17") (pinfunction "PB5(SCK)_17") (pintype "bidirectional"))
    )
    (net (code "125") (name "STEP-EN_LED") (class "Default")
      (node (ref "R49") (pin "2") (pinfunction "2_2") (pintype "passive"))
      (node (ref "U3") (pin "4") (pinfunction "Y_4") (pintype "bidirectional"))
    )
    (net (code "126") (name "STEP_ENABLE") (class "Default")
      (node (ref "JP19") (pin "6") (pinfunction "6_6") (pintype "passive"))
      (node (ref "U3") (pin "2") (pinfunction "A_2") (pintype "bidirectional"))
      (node (ref "U5") (pin "26") (pinfunction "ENABLEN_26") (pintype "bidirectional"))
      (node (ref "U7") (pin "4") (pinfunction "Y_4") (pintype "bidirectional"))
      (node (ref "U8") (pin "26") (pinfunction "ENABLEN_26") (pintype "bidirectional"))
      (node (ref "U9") (pin "26") (pinfunction "ENABLEN_26") (pintype "bidirectional"))
    )
    (net (code "127") (name "TXO") (class "Default")
      (node (ref "JP2") (pin "22") (pinfunction "22_22") (pintype "passive"))
      (node (ref "R57") (pin "1") (pinfunction "1_1") (pintype "passive"))
      (node (ref "U1") (pin "31") (pinfunction "PD1(TXD)_31") (pintype "bidirectional"))
    )
    (net (code "128") (name "VCC") (class "Default")
      (node (ref "C42") (pin "1") (pinfunction "1_1") (pintype "passive"))
      (node (ref "JP15") (pin "2") (pinfunction "2_2") (pintype "passive"))
      (node (ref "JP2") (pin "5") (pinfunction "5_5") (pintype "passive"))
      (node (ref "JP2") (pin "7") (pinfunction "7_7") (pintype "passive"))
      (node (ref "U10") (pin "2") (pinfunction "OUT_2") (pintype "passive"))
    )
    (net (code "129") (name "VCC_USB") (class "Default")
      (node (ref "C53") (pin "1") (pinfunction "1_1") (pintype "passive"))
      (node (ref "F1") (pin "1") (pinfunction "1_1") (pintype "bidirectional"))
      (node (ref "JP5") (pin "VBUS") (pinfunction "VBUS_VBUS") (pintype "bidirectional"))
      (node (ref "U2") (pin "20") (pinfunction "VCC_20") (pintype "power_in"))
      (node (ref "U2") (pin "4") (pinfunction "VCCIO_4") (pintype "power_in"))
    )
    (net (code "130") (name "VIN") (class "Default")
      (node (ref "C14") (pin "+") (pinfunction "+_+") (pintype "passive"))
      (node (ref "C17") (pin "1") (pinfunction "1_1") (pintype "passive"))
      (node (ref "C2") (pin "2") (pinfunction "2_2") (pintype "passive"))
      (node (ref "C23") (pin "+") (pinfunction "+_+") (pintype "passive"))
      (node (ref "C25") (pin "+") (pinfunction "+_+") (pintype "passive"))
      (node (ref "C26") (pin "+") (pinfunction "+_+") (pintype "passive"))
      (node (ref "C28") (pin "1") (pinfunction "1_1") (pintype "passive"))
      (node (ref "C35") (pin "+") (pinfunction "+_+") (pintype "passive"))
      (node (ref "C38") (pin "+") (pinfunction "+_+") (pintype "passive"))
      (node (ref "C4") (pin "1") (pinfunction "1_1") (pintype "passive"))
      (node (ref "C41") (pin "+") (pinfunction "+_+") (pintype "passive"))
      (node (ref "C43") (pin "1") (pinfunction "1_1") (pintype "passive"))
      (node (ref "C45") (pin "1") (pinfunction "1_1") (pintype "passive"))
      (node (ref "C46") (pin "1") (pinfunction "1_1") (pintype "passive"))
      (node (ref "C6") (pin "1") (pinfunction "1_1") (pintype "passive"))
      (node (ref "JP19") (pin "4") (pinfunction "4_4") (pintype "passive"))
      (node (ref "JP19") (pin "5") (pinfunction "5_5") (pintype "passive"))
      (node (ref "JP2") (pin "1") (pinfunction "1_1") (pintype "passive"))
      (node (ref "JP2") (pin "3") (pinfunction "3_3") (pintype "passive"))
      (node (ref "JP6") (pin "PWR") (pinfunction "PWR_PWR") (pintype "bidirectional"))
      (node (ref "R50") (pin "1") (pinfunction "1_1") (pintype "passive"))
      (node (ref "R51") (pin "1") (pinfunction "1_1") (pintype "passive"))
      (node (ref "R55") (pin "2") (pinfunction "2_2") (pintype "passive"))
      (node (ref "R56") (pin "1") (pinfunction "1_1") (pintype "passive"))
      (node (ref "U10") (pin "1") (pinfunction "IN_1") (pintype "input"))
      (node (ref "U4") (pin "1") (pinfunction "VIN_1") (pintype "bidirectional"))
      (node (ref "U5") (pin "15") (pinfunction "VMB_15") (pintype "bidirectional"))
      (node (ref "U5") (pin "28") (pinfunction "VMA_28") (pintype "bidirectional"))
      (node (ref "U8") (pin "15") (pinfunction "VMB_15") (pintype "bidirectional"))
      (node (ref "U8") (pin "28") (pinfunction "VMA_28") (pintype "bidirectional"))
      (node (ref "U9") (pin "15") (pinfunction "VMB_15") (pintype "bidirectional"))
      (node (ref "U9") (pin "28") (pinfunction "VMA_28") (pintype "bidirectional"))
      (node (ref "VIN") (pin "2") (pinfunction "2_2") (pintype "passive"))
    )
    (net (code "131") (name "X_LIM") (class "Default")
      (node (ref "C54") (pin "1") (pinfunction "1_1") (pintype "passive"))
      (node (ref "R30") (pin "2") (pinfunction "2_2") (pintype "passive"))
      (node (ref "U6") (pin "1") (pinfunction "1A_1") (pintype "input"))
    )
    (net (code "132") (name "Y_LIM") (class "Default")
      (node (ref "C55") (pin "1") (pinfunction "1_1") (pintype "passive"))
      (node (ref "R33") (pin "2") (pinfunction "2_2") (pintype "passive"))
      (node (ref "U6") (pin "3") (pinfunction "2A_3") (pintype "input"))
    )
    (net (code "133") (name "Z_LIM") (class "Default")
      (node (ref "C56") (pin "1") (pinfunction "1_1") (pintype "passive"))
      (node (ref "R34") (pin "2") (pinfunction "2_2") (pintype "passive"))
      (node (ref "U6") (pin "5") (pinfunction "3A_5") (pintype "input"))
    )
    (net (code "134") (name "unconnected-(JP6-PadGNDBREAK)") (class "Default")
      (node (ref "JP6") (pin "GNDBREAK") (pinfunction "GNDBREAK_GNDBREAK") (pintype "bidirectional"))
    )
    (net (code "135") (name "unconnected-(U2-CTS-Pad11)") (class "Default")
      (node (ref "U2") (pin "11") (pinfunction "CTS_11") (pintype "input"))
    )
    (net (code "136") (name "unconnected-(U2-DCD-Pad10)") (class "Default")
      (node (ref "U2") (pin "10") (pinfunction "DCD_10") (pintype "input"))
    )
    (net (code "137") (name "unconnected-(U2-DSR-Pad9)") (class "Default")
      (node (ref "U2") (pin "9") (pinfunction "DSR_9") (pintype "input"))
    )
    (net (code "138") (name "unconnected-(U2-OSCI-Pad27)") (class "Default")
      (node (ref "U2") (pin "27") (pinfunction "OSCI_27") (pintype "input"))
    )
    (net (code "139") (name "unconnected-(U2-OSCO-Pad28)") (class "Default")
      (node (ref "U2") (pin "28") (pinfunction "OSCO_28") (pintype "output"))
    )
    (net (code "140") (name "unconnected-(U2-PWREN-Pad14)") (class "Default")
      (node (ref "U2") (pin "14") (pinfunction "PWREN_14") (pintype "input"))
    )
    (net (code "141") (name "unconnected-(U2-RESET-Pad19)") (class "Default")
      (node (ref "U2") (pin "19") (pinfunction "RESET_19") (pintype "input"))
    )
    (net (code "142") (name "unconnected-(U2-RI-Pad6)") (class "Default")
      (node (ref "U2") (pin "6") (pinfunction "RI_6") (pintype "input"))
    )
    (net (code "143") (name "unconnected-(U2-RTS-Pad3)") (class "Default")
      (node (ref "U2") (pin "3") (pinfunction "RTS_3") (pintype "output"))
    )
    (net (code "144") (name "unconnected-(U2-SLEEP-Pad12)") (class "Default")
      (node (ref "U2") (pin "12") (pinfunction "SLEEP_12") (pintype "input"))
    )
    (net (code "145") (name "unconnected-(U2-TXDEN-Pad13)") (class "Default")
      (node (ref "U2") (pin "13") (pinfunction "TXDEN_13") (pintype "input"))
    )
    (net (code "146") (name "unconnected-(U3-NC-Pad1)") (class "Default")
      (node (ref "U3") (pin "1") (pinfunction "NC_1") (pintype "bidirectional"))
    )
    (net (code "147") (name "unconnected-(U4-PGD-Pad3)") (class "Default")
      (node (ref "U4") (pin "3") (pinfunction "PGD_3") (pintype "bidirectional"))
    )
    (net (code "148") (name "unconnected-(U5-HOME-Pad2)") (class "Default")
      (node (ref "U5") (pin "2") (pinfunction "HOME_2") (pintype "bidirectional"))
    )
    (net (code "149") (name "unconnected-(U6-6Y-Pad12)") (class "Default")
      (node (ref "U6") (pin "12") (pinfunction "6Y_12") (pintype "output"))
    )
    (net (code "150") (name "unconnected-(U8-HOME-Pad2)") (class "Default")
      (node (ref "U8") (pin "2") (pinfunction "HOME_2") (pintype "bidirectional"))
    )
    (net (code "151") (name "unconnected-(U9-HOME-Pad2)") (class "Default")
      (node (ref "U9") (pin "2") (pinfunction "HOME_2") (pintype "bidirectional"))
    )
  )
)
